# Sheet_1_2024-11-01.net
KiCad netlist of a schematic drawn in Altium Designer
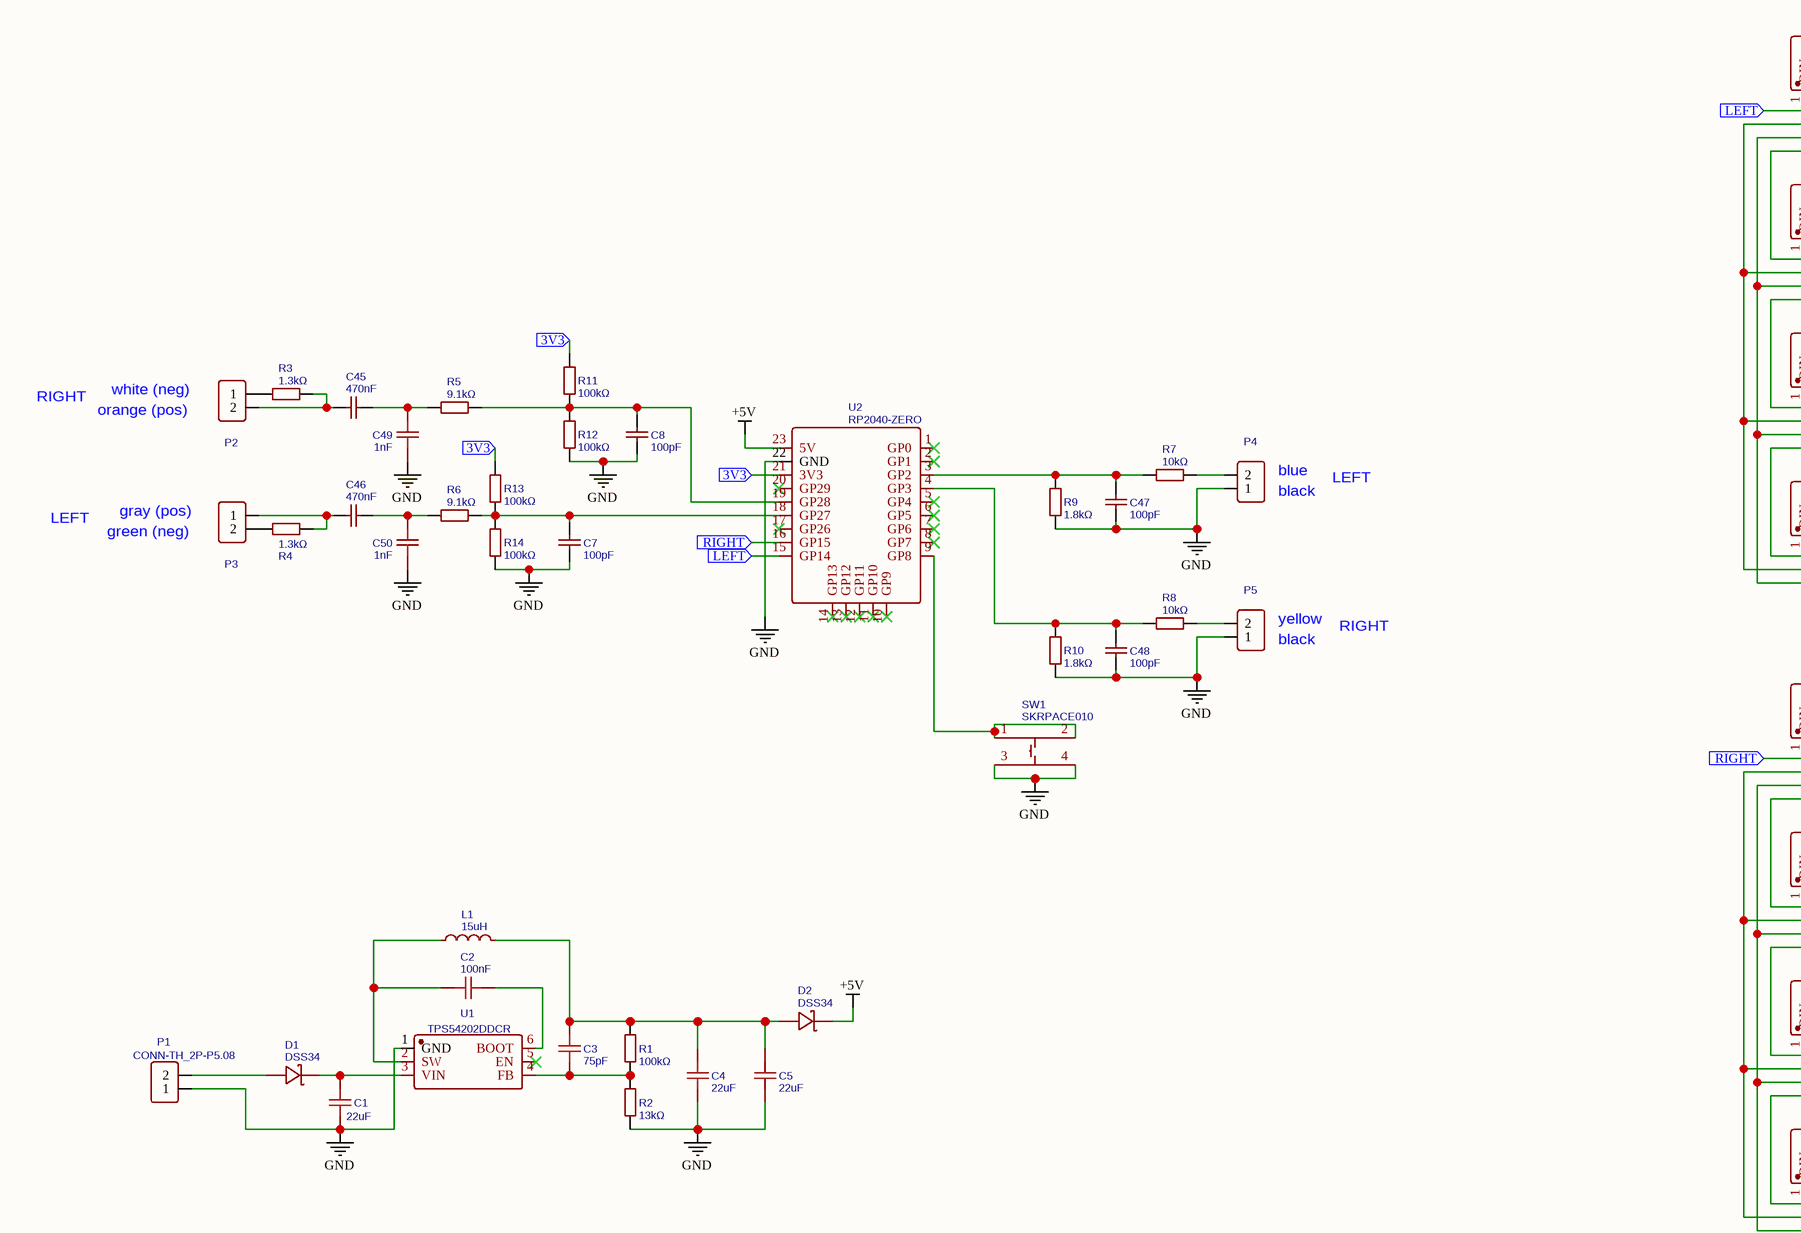
[diagram p0: Sheet_1_2024-11-01.schdoc, left]
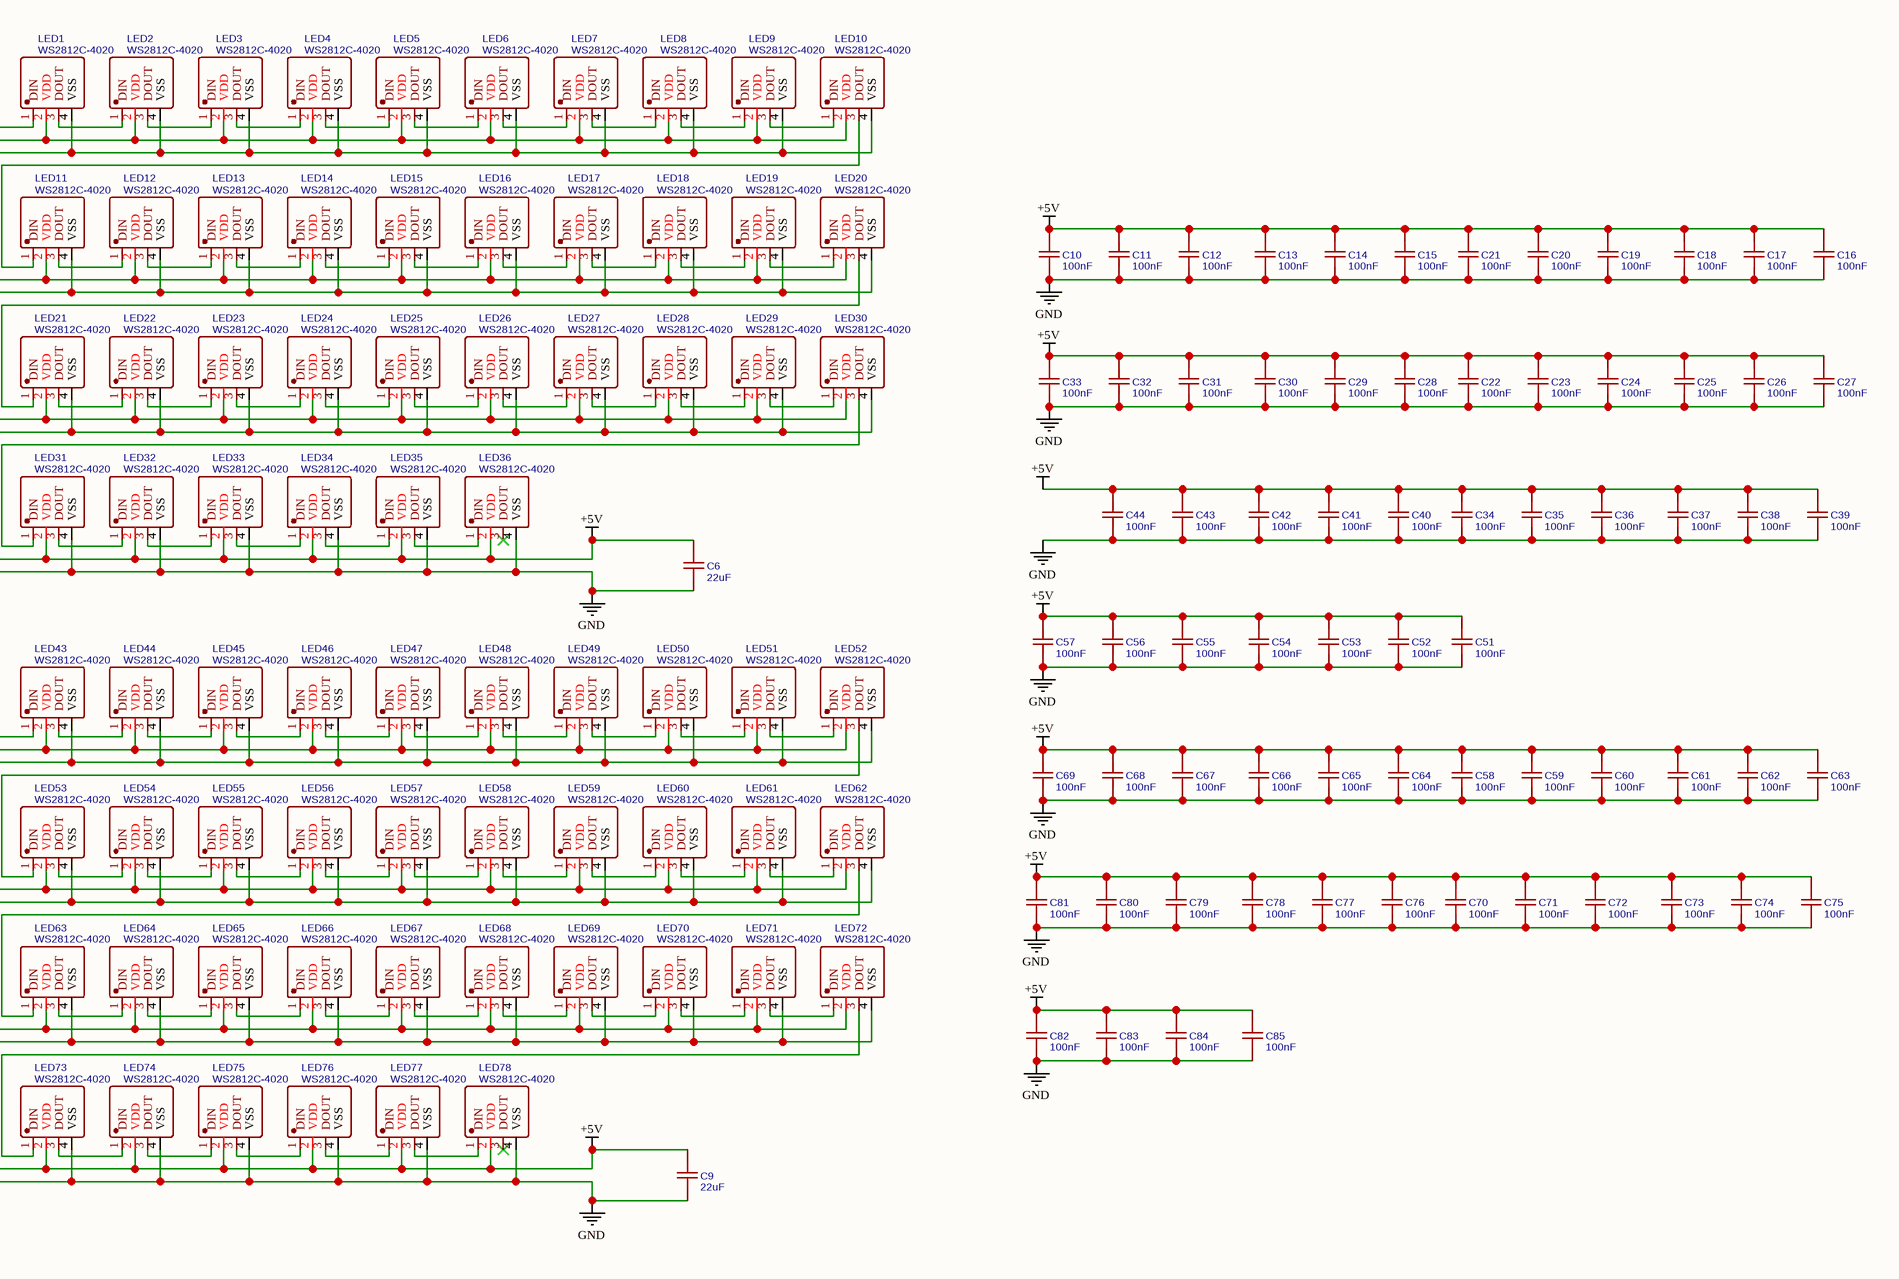
[diagram p1: Sheet_1_2024-11-01.schdoc, right]

(export (version "E")
  (design (tool "Eeschema 10.0.6"))
  (components
    (comp (ref "C1")
      (value "22uF")
      (fields
        (field (name "MANUFACTURER") "Samsung Electro-Mechanics")
        (field (name "MANUFACTURER PART") "CL21A226MAYNNNE")
        (field (name "CONTRIBUTOR") "LCSC")
      )
      (libsource (lib "altium-import") (part "root_1_22uF_"))
    )
    (comp (ref "C2")
      (value "100nF")
      (fields
        (field (name "MANUFACTURER PART") "CL05B104KO5NNNC")
        (field (name "MANUFACTURER") "SAMSUNG(三星)")
      )
      (libsource (lib "altium-import") (part "root_2_100nF_"))
    )
    (comp (ref "C3")
      (value "75pF")
      (fields
        (field (name "MANUFACTURER") "YAGEO(国巨)")
        (field (name "MANUFACTURER PART") "CC0603JRNPO9BN750")
        (field (name "CONTRIBUTOR") "LCSC")
      )
      (libsource (lib "altium-import") (part "root_0_75pF_"))
    )
    (comp (ref "C4")
      (value "22uF")
      (fields (field (name "MANUFACTURER") "SAMSUNG") (field (name "MANUFACTURER PART") "CL10A226MQ8NRNC"))
      (libsource (lib "altium-import") (part "root_1_22uF_"))
    )
    (comp (ref "C5")
      (value "22uF")
      (fields (field (name "MANUFACTURER") "SAMSUNG") (field (name "MANUFACTURER PART") "CL10A226MQ8NRNC"))
      (libsource (lib "altium-import") (part "root_1_22uF_"))
    )
    (comp (ref "C6")
      (value "22uF")
      (fields (field (name "MANUFACTURER") "SAMSUNG") (field (name "MANUFACTURER PART") "CL10A226MQ8NRNC"))
      (libsource (lib "altium-import") (part "root_1_22uF_"))
    )
    (comp (ref "C7")
      (value "100pF")
      (fields
        (field (name "MANUFACTURER PART") "CL10C101JB8NNNC")
        (field (name "MANUFACTURER") "SAMSUNG(三星)")
      )
      (libsource (lib "altium-import") (part "root_1_100pF_"))
    )
    (comp (ref "C8")
      (value "100pF")
      (fields
        (field (name "MANUFACTURER PART") "CL10C101JB8NNNC")
        (field (name "MANUFACTURER") "SAMSUNG(三星)")
      )
      (libsource (lib "altium-import") (part "root_1_100pF_"))
    )
    (comp (ref "C9")
      (value "22uF")
      (fields (field (name "MANUFACTURER") "SAMSUNG") (field (name "MANUFACTURER PART") "CL10A226MQ8NRNC"))
      (libsource (lib "altium-import") (part "root_1_22uF_"))
    )
    (comp (ref "C10")
      (value "100nF")
      (fields
        (field (name "MANUFACTURER PART") "CL05B104KO5NNNC")
        (field (name "MANUFACTURER") "SAMSUNG(三星)")
      )
      (libsource (lib "altium-import") (part "root_1_100nF_"))
    )
    (comp (ref "C11")
      (value "100nF")
      (fields
        (field (name "MANUFACTURER PART") "CL05B104KO5NNNC")
        (field (name "MANUFACTURER") "SAMSUNG(三星)")
      )
      (libsource (lib "altium-import") (part "root_1_100nF_"))
    )
    (comp (ref "C12")
      (value "100nF")
      (fields
        (field (name "MANUFACTURER PART") "CL05B104KO5NNNC")
        (field (name "MANUFACTURER") "SAMSUNG(三星)")
      )
      (libsource (lib "altium-import") (part "root_1_100nF_"))
    )
    (comp (ref "C13")
      (value "100nF")
      (fields
        (field (name "MANUFACTURER PART") "CL05B104KO5NNNC")
        (field (name "MANUFACTURER") "SAMSUNG(三星)")
      )
      (libsource (lib "altium-import") (part "root_1_100nF_"))
    )
    (comp (ref "C14")
      (value "100nF")
      (fields
        (field (name "MANUFACTURER PART") "CL05B104KO5NNNC")
        (field (name "MANUFACTURER") "SAMSUNG(三星)")
      )
      (libsource (lib "altium-import") (part "root_1_100nF_"))
    )
    (comp (ref "C15")
      (value "100nF")
      (fields
        (field (name "MANUFACTURER PART") "CL05B104KO5NNNC")
        (field (name "MANUFACTURER") "SAMSUNG(三星)")
      )
      (libsource (lib "altium-import") (part "root_1_100nF_"))
    )
    (comp (ref "C16")
      (value "100nF")
      (fields
        (field (name "MANUFACTURER PART") "CL05B104KO5NNNC")
        (field (name "MANUFACTURER") "SAMSUNG(三星)")
      )
      (libsource (lib "altium-import") (part "root_1_100nF_"))
    )
    (comp (ref "C17")
      (value "100nF")
      (fields
        (field (name "MANUFACTURER PART") "CL05B104KO5NNNC")
        (field (name "MANUFACTURER") "SAMSUNG(三星)")
      )
      (libsource (lib "altium-import") (part "root_1_100nF_"))
    )
    (comp (ref "C18")
      (value "100nF")
      (fields
        (field (name "MANUFACTURER PART") "CL05B104KO5NNNC")
        (field (name "MANUFACTURER") "SAMSUNG(三星)")
      )
      (libsource (lib "altium-import") (part "root_1_100nF_"))
    )
    (comp (ref "C19")
      (value "100nF")
      (fields
        (field (name "MANUFACTURER PART") "CL05B104KO5NNNC")
        (field (name "MANUFACTURER") "SAMSUNG(三星)")
      )
      (libsource (lib "altium-import") (part "root_1_100nF_"))
    )
    (comp (ref "C20")
      (value "100nF")
      (fields
        (field (name "MANUFACTURER PART") "CL05B104KO5NNNC")
        (field (name "MANUFACTURER") "SAMSUNG(三星)")
      )
      (libsource (lib "altium-import") (part "root_1_100nF_"))
    )
    (comp (ref "C21")
      (value "100nF")
      (fields
        (field (name "MANUFACTURER PART") "CL05B104KO5NNNC")
        (field (name "MANUFACTURER") "SAMSUNG(三星)")
      )
      (libsource (lib "altium-import") (part "root_1_100nF_"))
    )
    (comp (ref "C22")
      (value "100nF")
      (fields
        (field (name "MANUFACTURER PART") "CL05B104KO5NNNC")
        (field (name "MANUFACTURER") "SAMSUNG(三星)")
      )
      (libsource (lib "altium-import") (part "root_1_100nF_"))
    )
    (comp (ref "C23")
      (value "100nF")
      (fields
        (field (name "MANUFACTURER PART") "CL05B104KO5NNNC")
        (field (name "MANUFACTURER") "SAMSUNG(三星)")
      )
      (libsource (lib "altium-import") (part "root_1_100nF_"))
    )
    (comp (ref "C24")
      (value "100nF")
      (fields
        (field (name "MANUFACTURER PART") "CL05B104KO5NNNC")
        (field (name "MANUFACTURER") "SAMSUNG(三星)")
      )
      (libsource (lib "altium-import") (part "root_1_100nF_"))
    )
    (comp (ref "C25")
      (value "100nF")
      (fields
        (field (name "MANUFACTURER PART") "CL05B104KO5NNNC")
        (field (name "MANUFACTURER") "SAMSUNG(三星)")
      )
      (libsource (lib "altium-import") (part "root_1_100nF_"))
    )
    (comp (ref "C26")
      (value "100nF")
      (fields
        (field (name "MANUFACTURER PART") "CL05B104KO5NNNC")
        (field (name "MANUFACTURER") "SAMSUNG(三星)")
      )
      (libsource (lib "altium-import") (part "root_1_100nF_"))
    )
    (comp (ref "C27")
      (value "100nF")
      (fields
        (field (name "MANUFACTURER PART") "CL05B104KO5NNNC")
        (field (name "MANUFACTURER") "SAMSUNG(三星)")
      )
      (libsource (lib "altium-import") (part "root_1_100nF_"))
    )
    (comp (ref "C28")
      (value "100nF")
      (fields
        (field (name "MANUFACTURER PART") "CL05B104KO5NNNC")
        (field (name "MANUFACTURER") "SAMSUNG(三星)")
      )
      (libsource (lib "altium-import") (part "root_1_100nF_"))
    )
    (comp (ref "C29")
      (value "100nF")
      (fields
        (field (name "MANUFACTURER PART") "CL05B104KO5NNNC")
        (field (name "MANUFACTURER") "SAMSUNG(三星)")
      )
      (libsource (lib "altium-import") (part "root_1_100nF_"))
    )
    (comp (ref "C30")
      (value "100nF")
      (fields
        (field (name "MANUFACTURER PART") "CL05B104KO5NNNC")
        (field (name "MANUFACTURER") "SAMSUNG(三星)")
      )
      (libsource (lib "altium-import") (part "root_1_100nF_"))
    )
    (comp (ref "C31")
      (value "100nF")
      (fields
        (field (name "MANUFACTURER PART") "CL05B104KO5NNNC")
        (field (name "MANUFACTURER") "SAMSUNG(三星)")
      )
      (libsource (lib "altium-import") (part "root_1_100nF_"))
    )
    (comp (ref "C32")
      (value "100nF")
      (fields
        (field (name "MANUFACTURER PART") "CL05B104KO5NNNC")
        (field (name "MANUFACTURER") "SAMSUNG(三星)")
      )
      (libsource (lib "altium-import") (part "root_1_100nF_"))
    )
    (comp (ref "C33")
      (value "100nF")
      (fields
        (field (name "MANUFACTURER PART") "CL05B104KO5NNNC")
        (field (name "MANUFACTURER") "SAMSUNG(三星)")
      )
      (libsource (lib "altium-import") (part "root_1_100nF_"))
    )
    (comp (ref "C34")
      (value "100nF")
      (fields
        (field (name "MANUFACTURER PART") "CL05B104KO5NNNC")
        (field (name "MANUFACTURER") "SAMSUNG(三星)")
      )
      (libsource (lib "altium-import") (part "root_1_100nF_"))
    )
    (comp (ref "C35")
      (value "100nF")
      (fields
        (field (name "MANUFACTURER PART") "CL05B104KO5NNNC")
        (field (name "MANUFACTURER") "SAMSUNG(三星)")
      )
      (libsource (lib "altium-import") (part "root_1_100nF_"))
    )
    (comp (ref "C36")
      (value "100nF")
      (fields
        (field (name "MANUFACTURER PART") "CL05B104KO5NNNC")
        (field (name "MANUFACTURER") "SAMSUNG(三星)")
      )
      (libsource (lib "altium-import") (part "root_1_100nF_"))
    )
    (comp (ref "C37")
      (value "100nF")
      (fields
        (field (name "MANUFACTURER PART") "CL05B104KO5NNNC")
        (field (name "MANUFACTURER") "SAMSUNG(三星)")
      )
      (libsource (lib "altium-import") (part "root_1_100nF_"))
    )
    (comp (ref "C38")
      (value "100nF")
      (fields
        (field (name "MANUFACTURER PART") "CL05B104KO5NNNC")
        (field (name "MANUFACTURER") "SAMSUNG(三星)")
      )
      (libsource (lib "altium-import") (part "root_1_100nF_"))
    )
    (comp (ref "C39")
      (value "100nF")
      (fields
        (field (name "MANUFACTURER PART") "CL05B104KO5NNNC")
        (field (name "MANUFACTURER") "SAMSUNG(三星)")
      )
      (libsource (lib "altium-import") (part "root_1_100nF_"))
    )
    (comp (ref "C40")
      (value "100nF")
      (fields
        (field (name "MANUFACTURER PART") "CL05B104KO5NNNC")
        (field (name "MANUFACTURER") "SAMSUNG(三星)")
      )
      (libsource (lib "altium-import") (part "root_1_100nF_"))
    )
    (comp (ref "C41")
      (value "100nF")
      (fields
        (field (name "MANUFACTURER PART") "CL05B104KO5NNNC")
        (field (name "MANUFACTURER") "SAMSUNG(三星)")
      )
      (libsource (lib "altium-import") (part "root_1_100nF_"))
    )
    (comp (ref "C42")
      (value "100nF")
      (fields
        (field (name "MANUFACTURER PART") "CL05B104KO5NNNC")
        (field (name "MANUFACTURER") "SAMSUNG(三星)")
      )
      (libsource (lib "altium-import") (part "root_1_100nF_"))
    )
    (comp (ref "C43")
      (value "100nF")
      (fields
        (field (name "MANUFACTURER PART") "CL05B104KO5NNNC")
        (field (name "MANUFACTURER") "SAMSUNG(三星)")
      )
      (libsource (lib "altium-import") (part "root_1_100nF_"))
    )
    (comp (ref "C44")
      (value "100nF")
      (fields
        (field (name "MANUFACTURER PART") "CL05B104KO5NNNC")
        (field (name "MANUFACTURER") "SAMSUNG(三星)")
      )
      (libsource (lib "altium-import") (part "root_1_100nF_"))
    )
    (comp (ref "C45")
      (value "470nF")
      (fields
        (field (name "MANUFACTURER PART") "CL21B474KBFNNNE")
        (field (name "MANUFACTURER") "SAMSUNG(三星)")
      )
      (libsource (lib "altium-import") (part "root_0_470nF_"))
    )
    (comp (ref "C46")
      (value "470nF")
      (fields
        (field (name "MANUFACTURER PART") "CL21B474KBFNNNE")
        (field (name "MANUFACTURER") "SAMSUNG(三星)")
      )
      (libsource (lib "altium-import") (part "root_0_470nF_"))
    )
    (comp (ref "C47")
      (value "100pF")
      (fields
        (field (name "MANUFACTURER PART") "CL10C101JB8NNNC")
        (field (name "MANUFACTURER") "SAMSUNG(三星)")
      )
      (libsource (lib "altium-import") (part "root_1_100pF_"))
    )
    (comp (ref "C48")
      (value "100pF")
      (fields
        (field (name "MANUFACTURER PART") "CL10C101JB8NNNC")
        (field (name "MANUFACTURER") "SAMSUNG(三星)")
      )
      (libsource (lib "altium-import") (part "root_1_100pF_"))
    )
    (comp (ref "C49")
      (value "1nF")
      (fields
        (field (name "MANUFACTURER") "SAMSUNG(三星)")
        (field (name "MANUFACTURER PART") "CL10C102JB8NNNC")
        (field (name "CONTRIBUTOR") "LCSC")
      )
      (libsource (lib "altium-import") (part "root_1_1nF_"))
    )
    (comp (ref "C50")
      (value "1nF")
      (fields
        (field (name "MANUFACTURER") "SAMSUNG(三星)")
        (field (name "MANUFACTURER PART") "CL10C102JB8NNNC")
        (field (name "CONTRIBUTOR") "LCSC")
      )
      (libsource (lib "altium-import") (part "root_1_1nF_"))
    )
    (comp (ref "C51")
      (value "100nF")
      (fields
        (field (name "MANUFACTURER PART") "CL05B104KO5NNNC")
        (field (name "MANUFACTURER") "SAMSUNG(三星)")
      )
      (libsource (lib "altium-import") (part "root_1_100nF_"))
    )
    (comp (ref "C52")
      (value "100nF")
      (fields
        (field (name "MANUFACTURER PART") "CL05B104KO5NNNC")
        (field (name "MANUFACTURER") "SAMSUNG(三星)")
      )
      (libsource (lib "altium-import") (part "root_1_100nF_"))
    )
    (comp (ref "C53")
      (value "100nF")
      (fields
        (field (name "MANUFACTURER PART") "CL05B104KO5NNNC")
        (field (name "MANUFACTURER") "SAMSUNG(三星)")
      )
      (libsource (lib "altium-import") (part "root_1_100nF_"))
    )
    (comp (ref "C54")
      (value "100nF")
      (fields
        (field (name "MANUFACTURER PART") "CL05B104KO5NNNC")
        (field (name "MANUFACTURER") "SAMSUNG(三星)")
      )
      (libsource (lib "altium-import") (part "root_1_100nF_"))
    )
    (comp (ref "C55")
      (value "100nF")
      (fields
        (field (name "MANUFACTURER PART") "CL05B104KO5NNNC")
        (field (name "MANUFACTURER") "SAMSUNG(三星)")
      )
      (libsource (lib "altium-import") (part "root_1_100nF_"))
    )
    (comp (ref "C56")
      (value "100nF")
      (fields
        (field (name "MANUFACTURER PART") "CL05B104KO5NNNC")
        (field (name "MANUFACTURER") "SAMSUNG(三星)")
      )
      (libsource (lib "altium-import") (part "root_1_100nF_"))
    )
    (comp (ref "C57")
      (value "100nF")
      (fields
        (field (name "MANUFACTURER PART") "CL05B104KO5NNNC")
        (field (name "MANUFACTURER") "SAMSUNG(三星)")
      )
      (libsource (lib "altium-import") (part "root_1_100nF_"))
    )
    (comp (ref "C58")
      (value "100nF")
      (fields
        (field (name "MANUFACTURER PART") "CL05B104KO5NNNC")
        (field (name "MANUFACTURER") "SAMSUNG(三星)")
      )
      (libsource (lib "altium-import") (part "root_1_100nF_"))
    )
    (comp (ref "C59")
      (value "100nF")
      (fields
        (field (name "MANUFACTURER PART") "CL05B104KO5NNNC")
        (field (name "MANUFACTURER") "SAMSUNG(三星)")
      )
      (libsource (lib "altium-import") (part "root_1_100nF_"))
    )
    (comp (ref "C60")
      (value "100nF")
      (fields
        (field (name "MANUFACTURER PART") "CL05B104KO5NNNC")
        (field (name "MANUFACTURER") "SAMSUNG(三星)")
      )
      (libsource (lib "altium-import") (part "root_1_100nF_"))
    )
    (comp (ref "C61")
      (value "100nF")
      (fields
        (field (name "MANUFACTURER PART") "CL05B104KO5NNNC")
        (field (name "MANUFACTURER") "SAMSUNG(三星)")
      )
      (libsource (lib "altium-import") (part "root_1_100nF_"))
    )
    (comp (ref "C62")
      (value "100nF")
      (fields
        (field (name "MANUFACTURER PART") "CL05B104KO5NNNC")
        (field (name "MANUFACTURER") "SAMSUNG(三星)")
      )
      (libsource (lib "altium-import") (part "root_1_100nF_"))
    )
    (comp (ref "C63")
      (value "100nF")
      (fields
        (field (name "MANUFACTURER PART") "CL05B104KO5NNNC")
        (field (name "MANUFACTURER") "SAMSUNG(三星)")
      )
      (libsource (lib "altium-import") (part "root_1_100nF_"))
    )
    (comp (ref "C64")
      (value "100nF")
      (fields
        (field (name "MANUFACTURER PART") "CL05B104KO5NNNC")
        (field (name "MANUFACTURER") "SAMSUNG(三星)")
      )
      (libsource (lib "altium-import") (part "root_1_100nF_"))
    )
    (comp (ref "C65")
      (value "100nF")
      (fields
        (field (name "MANUFACTURER PART") "CL05B104KO5NNNC")
        (field (name "MANUFACTURER") "SAMSUNG(三星)")
      )
      (libsource (lib "altium-import") (part "root_1_100nF_"))
    )
    (comp (ref "C66")
      (value "100nF")
      (fields
        (field (name "MANUFACTURER PART") "CL05B104KO5NNNC")
        (field (name "MANUFACTURER") "SAMSUNG(三星)")
      )
      (libsource (lib "altium-import") (part "root_1_100nF_"))
    )
    (comp (ref "C67")
      (value "100nF")
      (fields
        (field (name "MANUFACTURER PART") "CL05B104KO5NNNC")
        (field (name "MANUFACTURER") "SAMSUNG(三星)")
      )
      (libsource (lib "altium-import") (part "root_1_100nF_"))
    )
    (comp (ref "C68")
      (value "100nF")
      (fields
        (field (name "MANUFACTURER PART") "CL05B104KO5NNNC")
        (field (name "MANUFACTURER") "SAMSUNG(三星)")
      )
      (libsource (lib "altium-import") (part "root_1_100nF_"))
    )
    (comp (ref "C69")
      (value "100nF")
      (fields
        (field (name "MANUFACTURER PART") "CL05B104KO5NNNC")
        (field (name "MANUFACTURER") "SAMSUNG(三星)")
      )
      (libsource (lib "altium-import") (part "root_1_100nF_"))
    )
    (comp (ref "C70")
      (value "100nF")
      (fields
        (field (name "MANUFACTURER PART") "CL05B104KO5NNNC")
        (field (name "MANUFACTURER") "SAMSUNG(三星)")
      )
      (libsource (lib "altium-import") (part "root_1_100nF_"))
    )
    (comp (ref "C71")
      (value "100nF")
      (fields
        (field (name "MANUFACTURER PART") "CL05B104KO5NNNC")
        (field (name "MANUFACTURER") "SAMSUNG(三星)")
      )
      (libsource (lib "altium-import") (part "root_1_100nF_"))
    )
    (comp (ref "C72")
      (value "100nF")
      (fields
        (field (name "MANUFACTURER PART") "CL05B104KO5NNNC")
        (field (name "MANUFACTURER") "SAMSUNG(三星)")
      )
      (libsource (lib "altium-import") (part "root_1_100nF_"))
    )
    (comp (ref "C73")
      (value "100nF")
      (fields
        (field (name "MANUFACTURER PART") "CL05B104KO5NNNC")
        (field (name "MANUFACTURER") "SAMSUNG(三星)")
      )
      (libsource (lib "altium-import") (part "root_1_100nF_"))
    )
    (comp (ref "C74")
      (value "100nF")
      (fields
        (field (name "MANUFACTURER PART") "CL05B104KO5NNNC")
        (field (name "MANUFACTURER") "SAMSUNG(三星)")
      )
      (libsource (lib "altium-import") (part "root_1_100nF_"))
    )
    (comp (ref "C75")
      (value "100nF")
      (fields
        (field (name "MANUFACTURER PART") "CL05B104KO5NNNC")
        (field (name "MANUFACTURER") "SAMSUNG(三星)")
      )
      (libsource (lib "altium-import") (part "root_1_100nF_"))
    )
    (comp (ref "C76")
      (value "100nF")
      (fields
        (field (name "MANUFACTURER PART") "CL05B104KO5NNNC")
        (field (name "MANUFACTURER") "SAMSUNG(三星)")
      )
      (libsource (lib "altium-import") (part "root_1_100nF_"))
    )
    (comp (ref "C77")
      (value "100nF")
      (fields
        (field (name "MANUFACTURER PART") "CL05B104KO5NNNC")
        (field (name "MANUFACTURER") "SAMSUNG(三星)")
      )
      (libsource (lib "altium-import") (part "root_1_100nF_"))
    )
    (comp (ref "C78")
      (value "100nF")
      (fields
        (field (name "MANUFACTURER PART") "CL05B104KO5NNNC")
        (field (name "MANUFACTURER") "SAMSUNG(三星)")
      )
      (libsource (lib "altium-import") (part "root_1_100nF_"))
    )
    (comp (ref "C79")
      (value "100nF")
      (fields
        (field (name "MANUFACTURER PART") "CL05B104KO5NNNC")
        (field (name "MANUFACTURER") "SAMSUNG(三星)")
      )
      (libsource (lib "altium-import") (part "root_1_100nF_"))
    )
    (comp (ref "C80")
      (value "100nF")
      (fields
        (field (name "MANUFACTURER PART") "CL05B104KO5NNNC")
        (field (name "MANUFACTURER") "SAMSUNG(三星)")
      )
      (libsource (lib "altium-import") (part "root_1_100nF_"))
    )
    (comp (ref "C81")
      (value "100nF")
      (fields
        (field (name "MANUFACTURER PART") "CL05B104KO5NNNC")
        (field (name "MANUFACTURER") "SAMSUNG(三星)")
      )
      (libsource (lib "altium-import") (part "root_1_100nF_"))
    )
    (comp (ref "C82")
      (value "100nF")
      (fields
        (field (name "MANUFACTURER PART") "CL05B104KO5NNNC")
        (field (name "MANUFACTURER") "SAMSUNG(三星)")
      )
      (libsource (lib "altium-import") (part "root_1_100nF_"))
    )
    (comp (ref "C83")
      (value "100nF")
      (fields
        (field (name "MANUFACTURER PART") "CL05B104KO5NNNC")
        (field (name "MANUFACTURER") "SAMSUNG(三星)")
      )
      (libsource (lib "altium-import") (part "root_1_100nF_"))
    )
    (comp (ref "C84")
      (value "100nF")
      (fields
        (field (name "MANUFACTURER PART") "CL05B104KO5NNNC")
        (field (name "MANUFACTURER") "SAMSUNG(三星)")
      )
      (libsource (lib "altium-import") (part "root_1_100nF_"))
    )
    (comp (ref "C85")
      (value "100nF")
      (fields
        (field (name "MANUFACTURER PART") "CL05B104KO5NNNC")
        (field (name "MANUFACTURER") "SAMSUNG(三星)")
      )
      (libsource (lib "altium-import") (part "root_1_100nF_"))
    )
    (comp (ref "D1")
      (value "DSS34")
      (fields (field (name "MANUFACTURER") "STARSEA"))
      (libsource (lib "altium-import") (part "root_2_DSS34_"))
    )
    (comp (ref "D2")
      (value "DSS34")
      (fields (field (name "MANUFACTURER") "STARSEA"))
      (libsource (lib "altium-import") (part "root_2_DSS34_"))
    )
    (comp (ref "L1")
      (value "15uH")
      (fields
        (field (name "MANUFACTURER") "Sunltech(韩国顺磁)")
        (field (name "MANUFACTURER PART") "SLP6028S150MTT")
        (field (name "CONTRIBUTOR") "LCSC")
      )
      (libsource (lib "altium-import") (part "root_0_15uH_"))
    )
    (comp (ref "LED1")
      (value "WS2812C-4020")
      (fields (field (name "MANUFACTURER") "worldsemi") (field (name "CONTRIBUTOR") "lcsc"))
      (libsource (lib "altium-import") (part "root_1_WS2812C-4020_"))
    )
    (comp (ref "LED2")
      (value "WS2812C-4020")
      (fields (field (name "MANUFACTURER") "worldsemi") (field (name "CONTRIBUTOR") "lcsc"))
      (libsource (lib "altium-import") (part "root_1_WS2812C-4020_"))
    )
    (comp (ref "LED3")
      (value "WS2812C-4020")
      (fields (field (name "MANUFACTURER") "worldsemi") (field (name "CONTRIBUTOR") "lcsc"))
      (libsource (lib "altium-import") (part "root_1_WS2812C-4020_"))
    )
    (comp (ref "LED4")
      (value "WS2812C-4020")
      (fields (field (name "MANUFACTURER") "worldsemi") (field (name "CONTRIBUTOR") "lcsc"))
      (libsource (lib "altium-import") (part "root_1_WS2812C-4020_"))
    )
    (comp (ref "LED5")
      (value "WS2812C-4020")
      (fields (field (name "MANUFACTURER") "worldsemi") (field (name "CONTRIBUTOR") "lcsc"))
      (libsource (lib "altium-import") (part "root_1_WS2812C-4020_"))
    )
    (comp (ref "LED6")
      (value "WS2812C-4020")
      (fields (field (name "MANUFACTURER") "worldsemi") (field (name "CONTRIBUTOR") "lcsc"))
      (libsource (lib "altium-import") (part "root_1_WS2812C-4020_"))
    )
    (comp (ref "LED7")
      (value "WS2812C-4020")
      (fields (field (name "MANUFACTURER") "worldsemi") (field (name "CONTRIBUTOR") "lcsc"))
      (libsource (lib "altium-import") (part "root_1_WS2812C-4020_"))
    )
    (comp (ref "LED8")
      (value "WS2812C-4020")
      (fields (field (name "MANUFACTURER") "worldsemi") (field (name "CONTRIBUTOR") "lcsc"))
      (libsource (lib "altium-import") (part "root_1_WS2812C-4020_"))
    )
    (comp (ref "LED9")
      (value "WS2812C-4020")
      (fields (field (name "MANUFACTURER") "worldsemi") (field (name "CONTRIBUTOR") "lcsc"))
      (libsource (lib "altium-import") (part "root_1_WS2812C-4020_"))
    )
    (comp (ref "LED10")
      (value "WS2812C-4020")
      (fields (field (name "MANUFACTURER") "worldsemi") (field (name "CONTRIBUTOR") "lcsc"))
      (libsource (lib "altium-import") (part "root_1_WS2812C-4020_"))
    )
    (comp (ref "LED11")
      (value "WS2812C-4020")
      (fields (field (name "MANUFACTURER") "worldsemi") (field (name "CONTRIBUTOR") "lcsc"))
      (libsource (lib "altium-import") (part "root_1_WS2812C-4020_"))
    )
    (comp (ref "LED12")
      (value "WS2812C-4020")
      (fields (field (name "MANUFACTURER") "worldsemi") (field (name "CONTRIBUTOR") "lcsc"))
      (libsource (lib "altium-import") (part "root_1_WS2812C-4020_"))
    )
    (comp (ref "LED13")
      (value "WS2812C-4020")
      (fields (field (name "MANUFACTURER") "worldsemi") (field (name "CONTRIBUTOR") "lcsc"))
      (libsource (lib "altium-import") (part "root_1_WS2812C-4020_"))
    )
    (comp (ref "LED14")
      (value "WS2812C-4020")
      (fields (field (name "MANUFACTURER") "worldsemi") (field (name "CONTRIBUTOR") "lcsc"))
      (libsource (lib "altium-import") (part "root_1_WS2812C-4020_"))
    )
    (comp (ref "LED15")
      (value "WS2812C-4020")
      (fields (field (name "MANUFACTURER") "worldsemi") (field (name "CONTRIBUTOR") "lcsc"))
      (libsource (lib "altium-import") (part "root_1_WS2812C-4020_"))
    )
    (comp (ref "LED16")
      (value "WS2812C-4020")
      (fields (field (name "MANUFACTURER") "worldsemi") (field (name "CONTRIBUTOR") "lcsc"))
      (libsource (lib "altium-import") (part "root_1_WS2812C-4020_"))
    )
    (comp (ref "LED17")
      (value "WS2812C-4020")
      (fields (field (name "MANUFACTURER") "worldsemi") (field (name "CONTRIBUTOR") "lcsc"))
      (libsource (lib "altium-import") (part "root_1_WS2812C-4020_"))
    )
    (comp (ref "LED18")
      (value "WS2812C-4020")
      (fields (field (name "MANUFACTURER") "worldsemi") (field (name "CONTRIBUTOR") "lcsc"))
      (libsource (lib "altium-import") (part "root_1_WS2812C-4020_"))
    )
    (comp (ref "LED19")
      (value "WS2812C-4020")
      (fields (field (name "MANUFACTURER") "worldsemi") (field (name "CONTRIBUTOR") "lcsc"))
      (libsource (lib "altium-import") (part "root_1_WS2812C-4020_"))
    )
    (comp (ref "LED20")
      (value "WS2812C-4020")
      (fields (field (name "MANUFACTURER") "worldsemi") (field (name "CONTRIBUTOR") "lcsc"))
      (libsource (lib "altium-import") (part "root_1_WS2812C-4020_"))
    )
    (comp (ref "LED21")
      (value "WS2812C-4020")
      (fields (field (name "MANUFACTURER") "worldsemi") (field (name "CONTRIBUTOR") "lcsc"))
      (libsource (lib "altium-import") (part "root_1_WS2812C-4020_"))
    )
    (comp (ref "LED22")
      (value "WS2812C-4020")
      (fields (field (name "MANUFACTURER") "worldsemi") (field (name "CONTRIBUTOR") "lcsc"))
      (libsource (lib "altium-import") (part "root_1_WS2812C-4020_"))
    )
    (comp (ref "LED23")
      (value "WS2812C-4020")
      (fields (field (name "MANUFACTURER") "worldsemi") (field (name "CONTRIBUTOR") "lcsc"))
      (libsource (lib "altium-import") (part "root_1_WS2812C-4020_"))
    )
    (comp (ref "LED24")
      (value "WS2812C-4020")
      (fields (field (name "MANUFACTURER") "worldsemi") (field (name "CONTRIBUTOR") "lcsc"))
      (libsource (lib "altium-import") (part "root_1_WS2812C-4020_"))
    )
    (comp (ref "LED25")
      (value "WS2812C-4020")
      (fields (field (name "MANUFACTURER") "worldsemi") (field (name "CONTRIBUTOR") "lcsc"))
      (libsource (lib "altium-import") (part "root_1_WS2812C-4020_"))
    )
    (comp (ref "LED26")
      (value "WS2812C-4020")
      (fields (field (name "MANUFACTURER") "worldsemi") (field (name "CONTRIBUTOR") "lcsc"))
      (libsource (lib "altium-import") (part "root_1_WS2812C-4020_"))
    )
    (comp (ref "LED27")
      (value "WS2812C-4020")
      (fields (field (name "MANUFACTURER") "worldsemi") (field (name "CONTRIBUTOR") "lcsc"))
      (libsource (lib "altium-import") (part "root_1_WS2812C-4020_"))
    )
    (comp (ref "LED28")
      (value "WS2812C-4020")
      (fields (field (name "MANUFACTURER") "worldsemi") (field (name "CONTRIBUTOR") "lcsc"))
      (libsource (lib "altium-import") (part "root_1_WS2812C-4020_"))
    )
    (comp (ref "LED29")
      (value "WS2812C-4020")
      (fields (field (name "MANUFACTURER") "worldsemi") (field (name "CONTRIBUTOR") "lcsc"))
      (libsource (lib "altium-import") (part "root_1_WS2812C-4020_"))
    )
    (comp (ref "LED30")
      (value "WS2812C-4020")
      (fields (field (name "MANUFACTURER") "worldsemi") (field (name "CONTRIBUTOR") "lcsc"))
      (libsource (lib "altium-import") (part "root_1_WS2812C-4020_"))
    )
    (comp (ref "LED31")
      (value "WS2812C-4020")
      (fields (field (name "MANUFACTURER") "worldsemi") (field (name "CONTRIBUTOR") "lcsc"))
      (libsource (lib "altium-import") (part "root_1_WS2812C-4020_"))
    )
    (comp (ref "LED32")
      (value "WS2812C-4020")
      (fields (field (name "MANUFACTURER") "worldsemi") (field (name "CONTRIBUTOR") "lcsc"))
      (libsource (lib "altium-import") (part "root_1_WS2812C-4020_"))
    )
    (comp (ref "LED33")
      (value "WS2812C-4020")
      (fields (field (name "MANUFACTURER") "worldsemi") (field (name "CONTRIBUTOR") "lcsc"))
      (libsource (lib "altium-import") (part "root_1_WS2812C-4020_"))
    )
    (comp (ref "LED34")
      (value "WS2812C-4020")
      (fields (field (name "MANUFACTURER") "worldsemi") (field (name "CONTRIBUTOR") "lcsc"))
      (libsource (lib "altium-import") (part "root_1_WS2812C-4020_"))
    )
    (comp (ref "LED35")
      (value "WS2812C-4020")
      (fields (field (name "MANUFACTURER") "worldsemi") (field (name "CONTRIBUTOR") "lcsc"))
      (libsource (lib "altium-import") (part "root_1_WS2812C-4020_"))
    )
    (comp (ref "LED36")
      (value "WS2812C-4020")
      (fields (field (name "MANUFACTURER") "worldsemi") (field (name "CONTRIBUTOR") "lcsc"))
      (libsource (lib "altium-import") (part "root_1_WS2812C-4020_"))
    )
    (comp (ref "LED43")
      (value "WS2812C-4020")
      (fields (field (name "MANUFACTURER") "worldsemi") (field (name "CONTRIBUTOR") "lcsc"))
      (libsource (lib "altium-import") (part "root_1_WS2812C-4020_"))
    )
    (comp (ref "LED44")
      (value "WS2812C-4020")
      (fields (field (name "MANUFACTURER") "worldsemi") (field (name "CONTRIBUTOR") "lcsc"))
      (libsource (lib "altium-import") (part "root_1_WS2812C-4020_"))
    )
    (comp (ref "LED45")
      (value "WS2812C-4020")
      (fields (field (name "MANUFACTURER") "worldsemi") (field (name "CONTRIBUTOR") "lcsc"))
      (libsource (lib "altium-import") (part "root_1_WS2812C-4020_"))
    )
    (comp (ref "LED46")
      (value "WS2812C-4020")
      (fields (field (name "MANUFACTURER") "worldsemi") (field (name "CONTRIBUTOR") "lcsc"))
      (libsource (lib "altium-import") (part "root_1_WS2812C-4020_"))
    )
    (comp (ref "LED47")
      (value "WS2812C-4020")
      (fields (field (name "MANUFACTURER") "worldsemi") (field (name "CONTRIBUTOR") "lcsc"))
      (libsource (lib "altium-import") (part "root_1_WS2812C-4020_"))
    )
    (comp (ref "LED48")
      (value "WS2812C-4020")
      (fields (field (name "MANUFACTURER") "worldsemi") (field (name "CONTRIBUTOR") "lcsc"))
      (libsource (lib "altium-import") (part "root_1_WS2812C-4020_"))
    )
    (comp (ref "LED49")
      (value "WS2812C-4020")
      (fields (field (name "MANUFACTURER") "worldsemi") (field (name "CONTRIBUTOR") "lcsc"))
      (libsource (lib "altium-import") (part "root_1_WS2812C-4020_"))
    )
    (comp (ref "LED50")
      (value "WS2812C-4020")
      (fields (field (name "MANUFACTURER") "worldsemi") (field (name "CONTRIBUTOR") "lcsc"))
      (libsource (lib "altium-import") (part "root_1_WS2812C-4020_"))
    )
    (comp (ref "LED51")
      (value "WS2812C-4020")
      (fields (field (name "MANUFACTURER") "worldsemi") (field (name "CONTRIBUTOR") "lcsc"))
      (libsource (lib "altium-import") (part "root_1_WS2812C-4020_"))
    )
    (comp (ref "LED52")
      (value "WS2812C-4020")
      (fields (field (name "MANUFACTURER") "worldsemi") (field (name "CONTRIBUTOR") "lcsc"))
      (libsource (lib "altium-import") (part "root_1_WS2812C-4020_"))
    )
    (comp (ref "LED53")
      (value "WS2812C-4020")
      (fields (field (name "MANUFACTURER") "worldsemi") (field (name "CONTRIBUTOR") "lcsc"))
      (libsource (lib "altium-import") (part "root_1_WS2812C-4020_"))
    )
    (comp (ref "LED54")
      (value "WS2812C-4020")
      (fields (field (name "MANUFACTURER") "worldsemi") (field (name "CONTRIBUTOR") "lcsc"))
      (libsource (lib "altium-import") (part "root_1_WS2812C-4020_"))
    )
    (comp (ref "LED55")
      (value "WS2812C-4020")
      (fields (field (name "MANUFACTURER") "worldsemi") (field (name "CONTRIBUTOR") "lcsc"))
      (libsource (lib "altium-import") (part "root_1_WS2812C-4020_"))
    )
    (comp (ref "LED56")
      (value "WS2812C-4020")
      (fields (field (name "MANUFACTURER") "worldsemi") (field (name "CONTRIBUTOR") "lcsc"))
      (libsource (lib "altium-import") (part "root_1_WS2812C-4020_"))
    )
    (comp (ref "LED57")
      (value "WS2812C-4020")
      (fields (field (name "MANUFACTURER") "worldsemi") (field (name "CONTRIBUTOR") "lcsc"))
      (libsource (lib "altium-import") (part "root_1_WS2812C-4020_"))
    )
    (comp (ref "LED58")
      (value "WS2812C-4020")
      (fields (field (name "MANUFACTURER") "worldsemi") (field (name "CONTRIBUTOR") "lcsc"))
      (libsource (lib "altium-import") (part "root_1_WS2812C-4020_"))
    )
    (comp (ref "LED59")
      (value "WS2812C-4020")
      (fields (field (name "MANUFACTURER") "worldsemi") (field (name "CONTRIBUTOR") "lcsc"))
      (libsource (lib "altium-import") (part "root_1_WS2812C-4020_"))
    )
    (comp (ref "LED60")
      (value "WS2812C-4020")
      (fields (field (name "MANUFACTURER") "worldsemi") (field (name "CONTRIBUTOR") "lcsc"))
      (libsource (lib "altium-import") (part "root_1_WS2812C-4020_"))
    )
    (comp (ref "LED61")
      (value "WS2812C-4020")
      (fields (field (name "MANUFACTURER") "worldsemi") (field (name "CONTRIBUTOR") "lcsc"))
      (libsource (lib "altium-import") (part "root_1_WS2812C-4020_"))
    )
    (comp (ref "LED62")
      (value "WS2812C-4020")
      (fields (field (name "MANUFACTURER") "worldsemi") (field (name "CONTRIBUTOR") "lcsc"))
      (libsource (lib "altium-import") (part "root_1_WS2812C-4020_"))
    )
    (comp (ref "LED63")
      (value "WS2812C-4020")
      (fields (field (name "MANUFACTURER") "worldsemi") (field (name "CONTRIBUTOR") "lcsc"))
      (libsource (lib "altium-import") (part "root_1_WS2812C-4020_"))
    )
    (comp (ref "LED64")
      (value "WS2812C-4020")
      (fields (field (name "MANUFACTURER") "worldsemi") (field (name "CONTRIBUTOR") "lcsc"))
      (libsource (lib "altium-import") (part "root_1_WS2812C-4020_"))
    )
    (comp (ref "LED65")
      (value "WS2812C-4020")
      (fields (field (name "MANUFACTURER") "worldsemi") (field (name "CONTRIBUTOR") "lcsc"))
      (libsource (lib "altium-import") (part "root_1_WS2812C-4020_"))
    )
    (comp (ref "LED66")
      (value "WS2812C-4020")
      (fields (field (name "MANUFACTURER") "worldsemi") (field (name "CONTRIBUTOR") "lcsc"))
      (libsource (lib "altium-import") (part "root_1_WS2812C-4020_"))
    )
    (comp (ref "LED67")
      (value "WS2812C-4020")
      (fields (field (name "MANUFACTURER") "worldsemi") (field (name "CONTRIBUTOR") "lcsc"))
      (libsource (lib "altium-import") (part "root_1_WS2812C-4020_"))
    )
    (comp (ref "LED68")
      (value "WS2812C-4020")
      (fields (field (name "MANUFACTURER") "worldsemi") (field (name "CONTRIBUTOR") "lcsc"))
      (libsource (lib "altium-import") (part "root_1_WS2812C-4020_"))
    )
    (comp (ref "LED69")
      (value "WS2812C-4020")
      (fields (field (name "MANUFACTURER") "worldsemi") (field (name "CONTRIBUTOR") "lcsc"))
      (libsource (lib "altium-import") (part "root_1_WS2812C-4020_"))
    )
    (comp (ref "LED70")
      (value "WS2812C-4020")
      (fields (field (name "MANUFACTURER") "worldsemi") (field (name "CONTRIBUTOR") "lcsc"))
      (libsource (lib "altium-import") (part "root_1_WS2812C-4020_"))
    )
    (comp (ref "LED71")
      (value "WS2812C-4020")
      (fields (field (name "MANUFACTURER") "worldsemi") (field (name "CONTRIBUTOR") "lcsc"))
      (libsource (lib "altium-import") (part "root_1_WS2812C-4020_"))
    )
    (comp (ref "LED72")
      (value "WS2812C-4020")
      (fields (field (name "MANUFACTURER") "worldsemi") (field (name "CONTRIBUTOR") "lcsc"))
      (libsource (lib "altium-import") (part "root_1_WS2812C-4020_"))
    )
    (comp (ref "LED73")
      (value "WS2812C-4020")
      (fields (field (name "MANUFACTURER") "worldsemi") (field (name "CONTRIBUTOR") "lcsc"))
      (libsource (lib "altium-import") (part "root_1_WS2812C-4020_"))
    )
    (comp (ref "LED74")
      (value "WS2812C-4020")
      (fields (field (name "MANUFACTURER") "worldsemi") (field (name "CONTRIBUTOR") "lcsc"))
      (libsource (lib "altium-import") (part "root_1_WS2812C-4020_"))
    )
    (comp (ref "LED75")
      (value "WS2812C-4020")
      (fields (field (name "MANUFACTURER") "worldsemi") (field (name "CONTRIBUTOR") "lcsc"))
      (libsource (lib "altium-import") (part "root_1_WS2812C-4020_"))
    )
    (comp (ref "LED76")
      (value "WS2812C-4020")
      (fields (field (name "MANUFACTURER") "worldsemi") (field (name "CONTRIBUTOR") "lcsc"))
      (libsource (lib "altium-import") (part "root_1_WS2812C-4020_"))
    )
    (comp (ref "LED77")
      (value "WS2812C-4020")
      (fields (field (name "MANUFACTURER") "worldsemi") (field (name "CONTRIBUTOR") "lcsc"))
      (libsource (lib "altium-import") (part "root_1_WS2812C-4020_"))
    )
    (comp (ref "LED78")
      (value "WS2812C-4020")
      (fields (field (name "MANUFACTURER") "worldsemi") (field (name "CONTRIBUTOR") "lcsc"))
      (libsource (lib "altium-import") (part "root_1_WS2812C-4020_"))
    )
    (comp (ref "P1")
      (value "CONN-TH_2P-P5.08")
      (fields (field (name "CONTRIBUTOR") "LCEDA_Lib"))
      (libsource (lib "") (part "root_2_CONN-TH_2P-P5.08__2"))
    )
    (comp (ref "P2")
      (value "CONN-TH_2P-P5.08")
      (fields (field (name "CONTRIBUTOR") "LCEDA_Lib"))
      (libsource (lib "altium-import") (part "root_2_CONN-TH_2P-P5.08_"))
    )
    (comp (ref "P3")
      (value "CONN-TH_2P-P5.08")
      (fields (field (name "CONTRIBUTOR") "LCEDA_Lib"))
      (libsource (lib "altium-import") (part "root_2_CONN-TH_2P-P5.08_"))
    )
    (comp (ref "P4")
      (value "CONN-TH_2P-P5.08")
      (fields (field (name "CONTRIBUTOR") "LCEDA_Lib"))
      (libsource (lib "") (part "root_2_CONN-TH_2P-P5.08__1"))
    )
    (comp (ref "P5")
      (value "CONN-TH_2P-P5.08")
      (fields (field (name "CONTRIBUTOR") "LCEDA_Lib"))
      (libsource (lib "") (part "root_2_CONN-TH_2P-P5.08__1"))
    )
    (comp (ref "R1")
      (value "100kΩ")
      (fields
        (field (name "MANUFACTURER") "UNI-ROYAL(厚声)")
        (field (name "MANUFACTURER PART") "0603WAF1003T5E")
      )
      (libsource (lib "altium-import") (part "root_1_100kΩ_"))
    )
    (comp (ref "R2")
      (value "13kΩ")
      (fields
        (field (name "MANUFACTURER") "UNI-ROYAL(厚声)")
        (field (name "MANUFACTURER PART") "0603WAF1302T5E")
      )
      (libsource (lib "altium-import") (part "root_1_13kΩ_"))
    )
    (comp (ref "R3")
      (value "1.3kΩ")
      (fields
        (field (name "MANUFACTURER") "UNI-ROYAL(厚声)")
        (field (name "MANUFACTURER PART") "0603WAF1301T5E")
      )
      (libsource (lib "altium-import") (part "root_0_1.3kΩ_"))
    )
    (comp (ref "R4")
      (value "1.3kΩ")
      (fields
        (field (name "MANUFACTURER") "UNI-ROYAL(厚声)")
        (field (name "MANUFACTURER PART") "0603WAF1301T5E")
      )
      (libsource (lib "altium-import") (part "root_0_1.3kΩ_"))
    )
    (comp (ref "R5")
      (value "9.1kΩ")
      (fields
        (field (name "MANUFACTURER") "UNI-ROYAL(厚声)")
        (field (name "MANUFACTURER PART") "0603WAF9101T5E")
      )
      (libsource (lib "altium-import") (part "root_0_9.1kΩ_"))
    )
    (comp (ref "R6")
      (value "9.1kΩ")
      (fields
        (field (name "MANUFACTURER") "UNI-ROYAL(厚声)")
        (field (name "MANUFACTURER PART") "0603WAF9101T5E")
      )
      (libsource (lib "altium-import") (part "root_0_9.1kΩ_"))
    )
    (comp (ref "R7")
      (value "10kΩ")
      (fields
        (field (name "MANUFACTURER") "UNI-ROYAL(厚声)")
        (field (name "MANUFACTURER PART") "0603WAF1002T5E")
      )
      (libsource (lib "altium-import") (part "root_0_10kΩ_"))
    )
    (comp (ref "R8")
      (value "10kΩ")
      (fields
        (field (name "MANUFACTURER") "UNI-ROYAL(厚声)")
        (field (name "MANUFACTURER PART") "0603WAF1002T5E")
      )
      (libsource (lib "altium-import") (part "root_0_10kΩ_"))
    )
    (comp (ref "R9")
      (value "1.8kΩ")
      (fields
        (field (name "MANUFACTURER") "UNI-ROYAL(厚声)")
        (field (name "MANUFACTURER PART") "0603WAF1801T5E")
      )
      (libsource (lib "altium-import") (part "root_1_1.8kΩ_"))
    )
    (comp (ref "R10")
      (value "1.8kΩ")
      (fields
        (field (name "MANUFACTURER") "UNI-ROYAL(厚声)")
        (field (name "MANUFACTURER PART") "0603WAF1801T5E")
      )
      (libsource (lib "altium-import") (part "root_1_1.8kΩ_"))
    )
    (comp (ref "R11")
      (value "100kΩ")
      (fields
        (field (name "MANUFACTURER") "UNI-ROYAL(厚声)")
        (field (name "MANUFACTURER PART") "0603WAF1003T5E")
      )
      (libsource (lib "altium-import") (part "root_1_100kΩ_"))
    )
    (comp (ref "R12")
      (value "100kΩ")
      (fields
        (field (name "MANUFACTURER") "UNI-ROYAL(厚声)")
        (field (name "MANUFACTURER PART") "0603WAF1003T5E")
      )
      (libsource (lib "altium-import") (part "root_1_100kΩ_"))
    )
    (comp (ref "R13")
      (value "100kΩ")
      (fields
        (field (name "MANUFACTURER") "UNI-ROYAL(厚声)")
        (field (name "MANUFACTURER PART") "0603WAF1003T5E")
      )
      (libsource (lib "altium-import") (part "root_1_100kΩ_"))
    )
    (comp (ref "R14")
      (value "100kΩ")
      (fields
        (field (name "MANUFACTURER") "UNI-ROYAL(厚声)")
        (field (name "MANUFACTURER PART") "0603WAF1003T5E")
      )
      (libsource (lib "altium-import") (part "root_1_100kΩ_"))
    )
    (comp (ref "SW1")
      (value "SKRPACE010")
      (fields (field (name "MANUFACTURER") "ALPSALPINE(阿尔卑斯阿尔派)") (field (name "CONTRIBUTOR") "LCSC"))
      (libsource (lib "altium-import") (part "root_0_SKRPACE010_"))
    )
    (comp (ref "U1")
      (value "TPS54202DDCR")
      (fields (field (name "MANUFACTURER") "TI(德州仪器)") (field (name "CONTRIBUTOR") "LCSC"))
      (libsource (lib "altium-import") (part "root_0_TPS54202DDCR_"))
    )
    (comp (ref "U2")
      (value "RP2040-ZERO")
      (fields
        (field (name "MANUFACTURER") "Waveshare(微雪电子)")
        (field (name "MANUFACTURER PART") "RP2040-Zero")
        (field (name "CONTRIBUTOR") "lcsc")
      )
      (libsource (lib "altium-import") (part "root_0_RP2040-ZERO_"))
    )
  )
  (nets
    (net (code "1") (name "+5V") (class "Default")
      (node (ref "C10") (pin "2") (pinfunction "2_2") (pintype "passive"))
      (node (ref "C11") (pin "2") (pinfunction "2_2") (pintype "passive"))
      (node (ref "C12") (pin "2") (pinfunction "2_2") (pintype "passive"))
      (node (ref "C13") (pin "2") (pinfunction "2_2") (pintype "passive"))
      (node (ref "C14") (pin "2") (pinfunction "2_2") (pintype "passive"))
      (node (ref "C15") (pin "2") (pinfunction "2_2") (pintype "passive"))
      (node (ref "C16") (pin "2") (pinfunction "2_2") (pintype "passive"))
      (node (ref "C17") (pin "2") (pinfunction "2_2") (pintype "passive"))
      (node (ref "C18") (pin "2") (pinfunction "2_2") (pintype "passive"))
      (node (ref "C19") (pin "2") (pinfunction "2_2") (pintype "passive"))
      (node (ref "C20") (pin "2") (pinfunction "2_2") (pintype "passive"))
      (node (ref "C21") (pin "2") (pinfunction "2_2") (pintype "passive"))
      (node (ref "C22") (pin "2") (pinfunction "2_2") (pintype "passive"))
      (node (ref "C23") (pin "2") (pinfunction "2_2") (pintype "passive"))
      (node (ref "C24") (pin "2") (pinfunction "2_2") (pintype "passive"))
      (node (ref "C25") (pin "2") (pinfunction "2_2") (pintype "passive"))
      (node (ref "C26") (pin "2") (pinfunction "2_2") (pintype "passive"))
      (node (ref "C27") (pin "2") (pinfunction "2_2") (pintype "passive"))
      (node (ref "C28") (pin "2") (pinfunction "2_2") (pintype "passive"))
      (node (ref "C29") (pin "2") (pinfunction "2_2") (pintype "passive"))
      (node (ref "C30") (pin "2") (pinfunction "2_2") (pintype "passive"))
      (node (ref "C31") (pin "2") (pinfunction "2_2") (pintype "passive"))
      (node (ref "C32") (pin "2") (pinfunction "2_2") (pintype "passive"))
      (node (ref "C33") (pin "2") (pinfunction "2_2") (pintype "passive"))
      (node (ref "C34") (pin "2") (pinfunction "2_2") (pintype "passive"))
      (node (ref "C35") (pin "2") (pinfunction "2_2") (pintype "passive"))
      (node (ref "C36") (pin "2") (pinfunction "2_2") (pintype "passive"))
      (node (ref "C37") (pin "2") (pinfunction "2_2") (pintype "passive"))
      (node (ref "C38") (pin "2") (pinfunction "2_2") (pintype "passive"))
      (node (ref "C39") (pin "2") (pinfunction "2_2") (pintype "passive"))
      (node (ref "C40") (pin "2") (pinfunction "2_2") (pintype "passive"))
      (node (ref "C41") (pin "2") (pinfunction "2_2") (pintype "passive"))
      (node (ref "C42") (pin "2") (pinfunction "2_2") (pintype "passive"))
      (node (ref "C43") (pin "2") (pinfunction "2_2") (pintype "passive"))
      (node (ref "C44") (pin "2") (pinfunction "2_2") (pintype "passive"))
      (node (ref "C51") (pin "2") (pinfunction "2_2") (pintype "passive"))
      (node (ref "C52") (pin "2") (pinfunction "2_2") (pintype "passive"))
      (node (ref "C53") (pin "2") (pinfunction "2_2") (pintype "passive"))
      (node (ref "C54") (pin "2") (pinfunction "2_2") (pintype "passive"))
      (node (ref "C55") (pin "2") (pinfunction "2_2") (pintype "passive"))
      (node (ref "C56") (pin "2") (pinfunction "2_2") (pintype "passive"))
      (node (ref "C57") (pin "2") (pinfunction "2_2") (pintype "passive"))
      (node (ref "C58") (pin "2") (pinfunction "2_2") (pintype "passive"))
      (node (ref "C59") (pin "2") (pinfunction "2_2") (pintype "passive"))
      (node (ref "C6") (pin "2") (pinfunction "2_2") (pintype "passive"))
      (node (ref "C60") (pin "2") (pinfunction "2_2") (pintype "passive"))
      (node (ref "C61") (pin "2") (pinfunction "2_2") (pintype "passive"))
      (node (ref "C62") (pin "2") (pinfunction "2_2") (pintype "passive"))
      (node (ref "C63") (pin "2") (pinfunction "2_2") (pintype "passive"))
      (node (ref "C64") (pin "2") (pinfunction "2_2") (pintype "passive"))
      (node (ref "C65") (pin "2") (pinfunction "2_2") (pintype "passive"))
      (node (ref "C66") (pin "2") (pinfunction "2_2") (pintype "passive"))
      (node (ref "C67") (pin "2") (pinfunction "2_2") (pintype "passive"))
      (node (ref "C68") (pin "2") (pinfunction "2_2") (pintype "passive"))
      (node (ref "C69") (pin "2") (pinfunction "2_2") (pintype "passive"))
      (node (ref "C70") (pin "2") (pinfunction "2_2") (pintype "passive"))
      (node (ref "C71") (pin "2") (pinfunction "2_2") (pintype "passive"))
      (node (ref "C72") (pin "2") (pinfunction "2_2") (pintype "passive"))
      (node (ref "C73") (pin "2") (pinfunction "2_2") (pintype "passive"))
      (node (ref "C74") (pin "2") (pinfunction "2_2") (pintype "passive"))
      (node (ref "C75") (pin "2") (pinfunction "2_2") (pintype "passive"))
      (node (ref "C76") (pin "2") (pinfunction "2_2") (pintype "passive"))
      (node (ref "C77") (pin "2") (pinfunction "2_2") (pintype "passive"))
      (node (ref "C78") (pin "2") (pinfunction "2_2") (pintype "passive"))
      (node (ref "C79") (pin "2") (pinfunction "2_2") (pintype "passive"))
      (node (ref "C80") (pin "2") (pinfunction "2_2") (pintype "passive"))
      (node (ref "C81") (pin "2") (pinfunction "2_2") (pintype "passive"))
      (node (ref "C82") (pin "2") (pinfunction "2_2") (pintype "passive"))
      (node (ref "C83") (pin "2") (pinfunction "2_2") (pintype "passive"))
      (node (ref "C84") (pin "2") (pinfunction "2_2") (pintype "passive"))
      (node (ref "C85") (pin "2") (pinfunction "2_2") (pintype "passive"))
      (node (ref "C9") (pin "2") (pinfunction "2_2") (pintype "passive"))
      (node (ref "D2") (pin "1") (pinfunction "K_1") (pintype "passive"))
      (node (ref "LED1") (pin "2") (pinfunction "VDD_2") (pintype "passive"))
      (node (ref "LED10") (pin "2") (pinfunction "VDD_2") (pintype "passive"))
      (node (ref "LED11") (pin "2") (pinfunction "VDD_2") (pintype "passive"))
      (node (ref "LED12") (pin "2") (pinfunction "VDD_2") (pintype "passive"))
      (node (ref "LED13") (pin "2") (pinfunction "VDD_2") (pintype "passive"))
      (node (ref "LED14") (pin "2") (pinfunction "VDD_2") (pintype "passive"))
      (node (ref "LED15") (pin "2") (pinfunction "VDD_2") (pintype "passive"))
      (node (ref "LED16") (pin "2") (pinfunction "VDD_2") (pintype "passive"))
      (node (ref "LED17") (pin "2") (pinfunction "VDD_2") (pintype "passive"))
      (node (ref "LED18") (pin "2") (pinfunction "VDD_2") (pintype "passive"))
      (node (ref "LED19") (pin "2") (pinfunction "VDD_2") (pintype "passive"))
      (node (ref "LED2") (pin "2") (pinfunction "VDD_2") (pintype "passive"))
      (node (ref "LED20") (pin "2") (pinfunction "VDD_2") (pintype "passive"))
      (node (ref "LED21") (pin "2") (pinfunction "VDD_2") (pintype "passive"))
      (node (ref "LED22") (pin "2") (pinfunction "VDD_2") (pintype "passive"))
      (node (ref "LED23") (pin "2") (pinfunction "VDD_2") (pintype "passive"))
      (node (ref "LED24") (pin "2") (pinfunction "VDD_2") (pintype "passive"))
      (node (ref "LED25") (pin "2") (pinfunction "VDD_2") (pintype "passive"))
      (node (ref "LED26") (pin "2") (pinfunction "VDD_2") (pintype "passive"))
      (node (ref "LED27") (pin "2") (pinfunction "VDD_2") (pintype "passive"))
      (node (ref "LED28") (pin "2") (pinfunction "VDD_2") (pintype "passive"))
      (node (ref "LED29") (pin "2") (pinfunction "VDD_2") (pintype "passive"))
      (node (ref "LED3") (pin "2") (pinfunction "VDD_2") (pintype "passive"))
      (node (ref "LED30") (pin "2") (pinfunction "VDD_2") (pintype "passive"))
      (node (ref "LED31") (pin "2") (pinfunction "VDD_2") (pintype "passive"))
      (node (ref "LED32") (pin "2") (pinfunction "VDD_2") (pintype "passive"))
      (node (ref "LED33") (pin "2") (pinfunction "VDD_2") (pintype "passive"))
      (node (ref "LED34") (pin "2") (pinfunction "VDD_2") (pintype "passive"))
      (node (ref "LED35") (pin "2") (pinfunction "VDD_2") (pintype "passive"))
      (node (ref "LED36") (pin "2") (pinfunction "VDD_2") (pintype "passive"))
      (node (ref "LED4") (pin "2") (pinfunction "VDD_2") (pintype "passive"))
      (node (ref "LED43") (pin "2") (pinfunction "VDD_2") (pintype "passive"))
      (node (ref "LED44") (pin "2") (pinfunction "VDD_2") (pintype "passive"))
      (node (ref "LED45") (pin "2") (pinfunction "VDD_2") (pintype "passive"))
      (node (ref "LED46") (pin "2") (pinfunction "VDD_2") (pintype "passive"))
      (node (ref "LED47") (pin "2") (pinfunction "VDD_2") (pintype "passive"))
      (node (ref "LED48") (pin "2") (pinfunction "VDD_2") (pintype "passive"))
      (node (ref "LED49") (pin "2") (pinfunction "VDD_2") (pintype "passive"))
      (node (ref "LED5") (pin "2") (pinfunction "VDD_2") (pintype "passive"))
      (node (ref "LED50") (pin "2") (pinfunction "VDD_2") (pintype "passive"))
      (node (ref "LED51") (pin "2") (pinfunction "VDD_2") (pintype "passive"))
      (node (ref "LED52") (pin "2") (pinfunction "VDD_2") (pintype "passive"))
      (node (ref "LED53") (pin "2") (pinfunction "VDD_2") (pintype "passive"))
      (node (ref "LED54") (pin "2") (pinfunction "VDD_2") (pintype "passive"))
      (node (ref "LED55") (pin "2") (pinfunction "VDD_2") (pintype "passive"))
      (node (ref "LED56") (pin "2") (pinfunction "VDD_2") (pintype "passive"))
      (node (ref "LED57") (pin "2") (pinfunction "VDD_2") (pintype "passive"))
      (node (ref "LED58") (pin "2") (pinfunction "VDD_2") (pintype "passive"))
      (node (ref "LED59") (pin "2") (pinfunction "VDD_2") (pintype "passive"))
      (node (ref "LED6") (pin "2") (pinfunction "VDD_2") (pintype "passive"))
      (node (ref "LED60") (pin "2") (pinfunction "VDD_2") (pintype "passive"))
      (node (ref "LED61") (pin "2") (pinfunction "VDD_2") (pintype "passive"))
      (node (ref "LED62") (pin "2") (pinfunction "VDD_2") (pintype "passive"))
      (node (ref "LED63") (pin "2") (pinfunction "VDD_2") (pintype "passive"))
      (node (ref "LED64") (pin "2") (pinfunction "VDD_2") (pintype "passive"))
      (node (ref "LED65") (pin "2") (pinfunction "VDD_2") (pintype "passive"))
      (node (ref "LED66") (pin "2") (pinfunction "VDD_2") (pintype "passive"))
      (node (ref "LED67") (pin "2") (pinfunction "VDD_2") (pintype "passive"))
      (node (ref "LED68") (pin "2") (pinfunction "VDD_2") (pintype "passive"))
      (node (ref "LED69") (pin "2") (pinfunction "VDD_2") (pintype "passive"))
      (node (ref "LED7") (pin "2") (pinfunction "VDD_2") (pintype "passive"))
      (node (ref "LED70") (pin "2") (pinfunction "VDD_2") (pintype "passive"))
      (node (ref "LED71") (pin "2") (pinfunction "VDD_2") (pintype "passive"))
      (node (ref "LED72") (pin "2") (pinfunction "VDD_2") (pintype "passive"))
      (node (ref "LED73") (pin "2") (pinfunction "VDD_2") (pintype "passive"))
      (node (ref "LED74") (pin "2") (pinfunction "VDD_2") (pintype "passive"))
      (node (ref "LED75") (pin "2") (pinfunction "VDD_2") (pintype "passive"))
      (node (ref "LED76") (pin "2") (pinfunction "VDD_2") (pintype "passive"))
      (node (ref "LED77") (pin "2") (pinfunction "VDD_2") (pintype "passive"))
      (node (ref "LED78") (pin "2") (pinfunction "VDD_2") (pintype "passive"))
      (node (ref "LED8") (pin "2") (pinfunction "VDD_2") (pintype "passive"))
      (node (ref "LED9") (pin "2") (pinfunction "VDD_2") (pintype "passive"))
      (node (ref "U2") (pin "23") (pinfunction "5V_23") (pintype "passive"))
    )
    (net (code "2") (name "/3V3") (class "Default")
      (node (ref "R11") (pin "2") (pinfunction "2_2") (pintype "passive"))
      (node (ref "R13") (pin "2") (pinfunction "2_2") (pintype "passive"))
      (node (ref "U2") (pin "21") (pinfunction "3V3_21") (pintype "passive"))
    )
    (net (code "3") (name "/LEFT") (class "Default")
      (node (ref "LED1") (pin "1") (pinfunction "DIN_1") (pintype "passive"))
      (node (ref "U2") (pin "15") (pinfunction "GP14_15") (pintype "passive"))
    )
    (net (code "4") (name "/RIGHT") (class "Default")
      (node (ref "LED43") (pin "1") (pinfunction "DIN_1") (pintype "passive"))
      (node (ref "U2") (pin "16") (pinfunction "GP15_16") (pintype "passive"))
    )
    (net (code "5") (name "GND") (class "Default")
      (node (ref "C1") (pin "1") (pinfunction "1_1") (pintype "passive"))
      (node (ref "C10") (pin "1") (pinfunction "1_1") (pintype "passive"))
      (node (ref "C11") (pin "1") (pinfunction "1_1") (pintype "passive"))
      (node (ref "C12") (pin "1") (pinfunction "1_1") (pintype "passive"))
      (node (ref "C13") (pin "1") (pinfunction "1_1") (pintype "passive"))
      (node (ref "C14") (pin "1") (pinfunction "1_1") (pintype "passive"))
      (node (ref "C15") (pin "1") (pinfunction "1_1") (pintype "passive"))
      (node (ref "C16") (pin "1") (pinfunction "1_1") (pintype "passive"))
      (node (ref "C17") (pin "1") (pinfunction "1_1") (pintype "passive"))
      (node (ref "C18") (pin "1") (pinfunction "1_1") (pintype "passive"))
      (node (ref "C19") (pin "1") (pinfunction "1_1") (pintype "passive"))
      (node (ref "C20") (pin "1") (pinfunction "1_1") (pintype "passive"))
      (node (ref "C21") (pin "1") (pinfunction "1_1") (pintype "passive"))
      (node (ref "C22") (pin "1") (pinfunction "1_1") (pintype "passive"))
      (node (ref "C23") (pin "1") (pinfunction "1_1") (pintype "passive"))
      (node (ref "C24") (pin "1") (pinfunction "1_1") (pintype "passive"))
      (node (ref "C25") (pin "1") (pinfunction "1_1") (pintype "passive"))
      (node (ref "C26") (pin "1") (pinfunction "1_1") (pintype "passive"))
      (node (ref "C27") (pin "1") (pinfunction "1_1") (pintype "passive"))
      (node (ref "C28") (pin "1") (pinfunction "1_1") (pintype "passive"))
      (node (ref "C29") (pin "1") (pinfunction "1_1") (pintype "passive"))
      (node (ref "C30") (pin "1") (pinfunction "1_1") (pintype "passive"))
      (node (ref "C31") (pin "1") (pinfunction "1_1") (pintype "passive"))
      (node (ref "C32") (pin "1") (pinfunction "1_1") (pintype "passive"))
      (node (ref "C33") (pin "1") (pinfunction "1_1") (pintype "passive"))
      (node (ref "C34") (pin "1") (pinfunction "1_1") (pintype "passive"))
      (node (ref "C35") (pin "1") (pinfunction "1_1") (pintype "passive"))
      (node (ref "C36") (pin "1") (pinfunction "1_1") (pintype "passive"))
      (node (ref "C37") (pin "1") (pinfunction "1_1") (pintype "passive"))
      (node (ref "C38") (pin "1") (pinfunction "1_1") (pintype "passive"))
      (node (ref "C39") (pin "1") (pinfunction "1_1") (pintype "passive"))
      (node (ref "C4") (pin "1") (pinfunction "1_1") (pintype "passive"))
      (node (ref "C40") (pin "1") (pinfunction "1_1") (pintype "passive"))
      (node (ref "C41") (pin "1") (pinfunction "1_1") (pintype "passive"))
      (node (ref "C42") (pin "1") (pinfunction "1_1") (pintype "passive"))
      (node (ref "C43") (pin "1") (pinfunction "1_1") (pintype "passive"))
      (node (ref "C44") (pin "1") (pinfunction "1_1") (pintype "passive"))
      (node (ref "C47") (pin "1") (pinfunction "1_1") (pintype "passive"))
      (node (ref "C48") (pin "1") (pinfunction "1_1") (pintype "passive"))
      (node (ref "C49") (pin "2") (pinfunction "2_2") (pintype "passive"))
      (node (ref "C5") (pin "1") (pinfunction "1_1") (pintype "passive"))
      (node (ref "C50") (pin "2") (pinfunction "2_2") (pintype "passive"))
      (node (ref "C51") (pin "1") (pinfunction "1_1") (pintype "passive"))
      (node (ref "C52") (pin "1") (pinfunction "1_1") (pintype "passive"))
      (node (ref "C53") (pin "1") (pinfunction "1_1") (pintype "passive"))
      (node (ref "C54") (pin "1") (pinfunction "1_1") (pintype "passive"))
      (node (ref "C55") (pin "1") (pinfunction "1_1") (pintype "passive"))
      (node (ref "C56") (pin "1") (pinfunction "1_1") (pintype "passive"))
      (node (ref "C57") (pin "1") (pinfunction "1_1") (pintype "passive"))
      (node (ref "C58") (pin "1") (pinfunction "1_1") (pintype "passive"))
      (node (ref "C59") (pin "1") (pinfunction "1_1") (pintype "passive"))
      (node (ref "C6") (pin "1") (pinfunction "1_1") (pintype "passive"))
      (node (ref "C60") (pin "1") (pinfunction "1_1") (pintype "passive"))
      (node (ref "C61") (pin "1") (pinfunction "1_1") (pintype "passive"))
      (node (ref "C62") (pin "1") (pinfunction "1_1") (pintype "passive"))
      (node (ref "C63") (pin "1") (pinfunction "1_1") (pintype "passive"))
      (node (ref "C64") (pin "1") (pinfunction "1_1") (pintype "passive"))
      (node (ref "C65") (pin "1") (pinfunction "1_1") (pintype "passive"))
      (node (ref "C66") (pin "1") (pinfunction "1_1") (pintype "passive"))
      (node (ref "C67") (pin "1") (pinfunction "1_1") (pintype "passive"))
      (node (ref "C68") (pin "1") (pinfunction "1_1") (pintype "passive"))
      (node (ref "C69") (pin "1") (pinfunction "1_1") (pintype "passive"))
      (node (ref "C7") (pin "1") (pinfunction "1_1") (pintype "passive"))
      (node (ref "C70") (pin "1") (pinfunction "1_1") (pintype "passive"))
      (node (ref "C71") (pin "1") (pinfunction "1_1") (pintype "passive"))
      (node (ref "C72") (pin "1") (pinfunction "1_1") (pintype "passive"))
      (node (ref "C73") (pin "1") (pinfunction "1_1") (pintype "passive"))
      (node (ref "C74") (pin "1") (pinfunction "1_1") (pintype "passive"))
      (node (ref "C75") (pin "1") (pinfunction "1_1") (pintype "passive"))
      (node (ref "C76") (pin "1") (pinfunction "1_1") (pintype "passive"))
      (node (ref "C77") (pin "1") (pinfunction "1_1") (pintype "passive"))
      (node (ref "C78") (pin "1") (pinfunction "1_1") (pintype "passive"))
      (node (ref "C79") (pin "1") (pinfunction "1_1") (pintype "passive"))
      (node (ref "C8") (pin "1") (pinfunction "1_1") (pintype "passive"))
      (node (ref "C80") (pin "1") (pinfunction "1_1") (pintype "passive"))
      (node (ref "C81") (pin "1") (pinfunction "1_1") (pintype "passive"))
      (node (ref "C82") (pin "1") (pinfunction "1_1") (pintype "passive"))
      (node (ref "C83") (pin "1") (pinfunction "1_1") (pintype "passive"))
      (node (ref "C84") (pin "1") (pinfunction "1_1") (pintype "passive"))
      (node (ref "C85") (pin "1") (pinfunction "1_1") (pintype "passive"))
      (node (ref "C9") (pin "1") (pinfunction "1_1") (pintype "passive"))
      (node (ref "LED1") (pin "4") (pinfunction "VSS_4") (pintype "passive"))
      (node (ref "LED10") (pin "4") (pinfunction "VSS_4") (pintype "passive"))
      (node (ref "LED11") (pin "4") (pinfunction "VSS_4") (pintype "passive"))
      (node (ref "LED12") (pin "4") (pinfunction "VSS_4") (pintype "passive"))
      (node (ref "LED13") (pin "4") (pinfunction "VSS_4") (pintype "passive"))
      (node (ref "LED14") (pin "4") (pinfunction "VSS_4") (pintype "passive"))
      (node (ref "LED15") (pin "4") (pinfunction "VSS_4") (pintype "passive"))
      (node (ref "LED16") (pin "4") (pinfunction "VSS_4") (pintype "passive"))
      (node (ref "LED17") (pin "4") (pinfunction "VSS_4") (pintype "passive"))
      (node (ref "LED18") (pin "4") (pinfunction "VSS_4") (pintype "passive"))
      (node (ref "LED19") (pin "4") (pinfunction "VSS_4") (pintype "passive"))
      (node (ref "LED2") (pin "4") (pinfunction "VSS_4") (pintype "passive"))
      (node (ref "LED20") (pin "4") (pinfunction "VSS_4") (pintype "passive"))
      (node (ref "LED21") (pin "4") (pinfunction "VSS_4") (pintype "passive"))
      (node (ref "LED22") (pin "4") (pinfunction "VSS_4") (pintype "passive"))
      (node (ref "LED23") (pin "4") (pinfunction "VSS_4") (pintype "passive"))
      (node (ref "LED24") (pin "4") (pinfunction "VSS_4") (pintype "passive"))
      (node (ref "LED25") (pin "4") (pinfunction "VSS_4") (pintype "passive"))
      (node (ref "LED26") (pin "4") (pinfunction "VSS_4") (pintype "passive"))
      (node (ref "LED27") (pin "4") (pinfunction "VSS_4") (pintype "passive"))
      (node (ref "LED28") (pin "4") (pinfunction "VSS_4") (pintype "passive"))
      (node (ref "LED29") (pin "4") (pinfunction "VSS_4") (pintype "passive"))
      (node (ref "LED3") (pin "4") (pinfunction "VSS_4") (pintype "passive"))
      (node (ref "LED30") (pin "4") (pinfunction "VSS_4") (pintype "passive"))
      (node (ref "LED31") (pin "4") (pinfunction "VSS_4") (pintype "passive"))
      (node (ref "LED32") (pin "4") (pinfunction "VSS_4") (pintype "passive"))
      (node (ref "LED33") (pin "4") (pinfunction "VSS_4") (pintype "passive"))
      (node (ref "LED34") (pin "4") (pinfunction "VSS_4") (pintype "passive"))
      (node (ref "LED35") (pin "4") (pinfunction "VSS_4") (pintype "passive"))
      (node (ref "LED36") (pin "4") (pinfunction "VSS_4") (pintype "passive"))
      (node (ref "LED4") (pin "4") (pinfunction "VSS_4") (pintype "passive"))
      (node (ref "LED43") (pin "4") (pinfunction "VSS_4") (pintype "passive"))
      (node (ref "LED44") (pin "4") (pinfunction "VSS_4") (pintype "passive"))
      (node (ref "LED45") (pin "4") (pinfunction "VSS_4") (pintype "passive"))
      (node (ref "LED46") (pin "4") (pinfunction "VSS_4") (pintype "passive"))
      (node (ref "LED47") (pin "4") (pinfunction "VSS_4") (pintype "passive"))
      (node (ref "LED48") (pin "4") (pinfunction "VSS_4") (pintype "passive"))
      (node (ref "LED49") (pin "4") (pinfunction "VSS_4") (pintype "passive"))
      (node (ref "LED5") (pin "4") (pinfunction "VSS_4") (pintype "passive"))
      (node (ref "LED50") (pin "4") (pinfunction "VSS_4") (pintype "passive"))
      (node (ref "LED51") (pin "4") (pinfunction "VSS_4") (pintype "passive"))
      (node (ref "LED52") (pin "4") (pinfunction "VSS_4") (pintype "passive"))
      (node (ref "LED53") (pin "4") (pinfunction "VSS_4") (pintype "passive"))
      (node (ref "LED54") (pin "4") (pinfunction "VSS_4") (pintype "passive"))
      (node (ref "LED55") (pin "4") (pinfunction "VSS_4") (pintype "passive"))
      (node (ref "LED56") (pin "4") (pinfunction "VSS_4") (pintype "passive"))
      (node (ref "LED57") (pin "4") (pinfunction "VSS_4") (pintype "passive"))
      (node (ref "LED58") (pin "4") (pinfunction "VSS_4") (pintype "passive"))
      (node (ref "LED59") (pin "4") (pinfunction "VSS_4") (pintype "passive"))
      (node (ref "LED6") (pin "4") (pinfunction "VSS_4") (pintype "passive"))
      (node (ref "LED60") (pin "4") (pinfunction "VSS_4") (pintype "passive"))
      (node (ref "LED61") (pin "4") (pinfunction "VSS_4") (pintype "passive"))
      (node (ref "LED62") (pin "4") (pinfunction "VSS_4") (pintype "passive"))
      (node (ref "LED63") (pin "4") (pinfunction "VSS_4") (pintype "passive"))
      (node (ref "LED64") (pin "4") (pinfunction "VSS_4") (pintype "passive"))
      (node (ref "LED65") (pin "4") (pinfunction "VSS_4") (pintype "passive"))
      (node (ref "LED66") (pin "4") (pinfunction "VSS_4") (pintype "passive"))
      (node (ref "LED67") (pin "4") (pinfunction "VSS_4") (pintype "passive"))
      (node (ref "LED68") (pin "4") (pinfunction "VSS_4") (pintype "passive"))
      (node (ref "LED69") (pin "4") (pinfunction "VSS_4") (pintype "passive"))
      (node (ref "LED7") (pin "4") (pinfunction "VSS_4") (pintype "passive"))
      (node (ref "LED70") (pin "4") (pinfunction "VSS_4") (pintype "passive"))
      (node (ref "LED71") (pin "4") (pinfunction "VSS_4") (pintype "passive"))
      (node (ref "LED72") (pin "4") (pinfunction "VSS_4") (pintype "passive"))
      (node (ref "LED73") (pin "4") (pinfunction "VSS_4") (pintype "passive"))
      (node (ref "LED74") (pin "4") (pinfunction "VSS_4") (pintype "passive"))
      (node (ref "LED75") (pin "4") (pinfunction "VSS_4") (pintype "passive"))
      (node (ref "LED76") (pin "4") (pinfunction "VSS_4") (pintype "passive"))
      (node (ref "LED77") (pin "4") (pinfunction "VSS_4") (pintype "passive"))
      (node (ref "LED78") (pin "4") (pinfunction "VSS_4") (pintype "passive"))
      (node (ref "LED8") (pin "4") (pinfunction "VSS_4") (pintype "passive"))
      (node (ref "LED9") (pin "4") (pinfunction "VSS_4") (pintype "passive"))
      (node (ref "P1") (pin "1") (pinfunction "1_1") (pintype "passive"))
      (node (ref "P4") (pin "1") (pinfunction "1_1") (pintype "passive"))
      (node (ref "P5") (pin "1") (pinfunction "1_1") (pintype "passive"))
      (node (ref "R10") (pin "1") (pinfunction "1_1") (pintype "passive"))
      (node (ref "R12") (pin "1") (pinfunction "1_1") (pintype "passive"))
      (node (ref "R14") (pin "1") (pinfunction "1_1") (pintype "passive"))
      (node (ref "R2") (pin "1") (pinfunction "1_1") (pintype "passive"))
      (node (ref "R9") (pin "1") (pinfunction "1_1") (pintype "passive"))
      (node (ref "SW1") (pin "3") (pinfunction "3_3") (pintype "passive"))
      (node (ref "SW1") (pin "4") (pinfunction "4_4") (pintype "passive"))
      (node (ref "U1") (pin "1") (pinfunction "GND_1") (pintype "passive"))
      (node (ref "U2") (pin "22") (pinfunction "GND_22") (pintype "passive"))
    )
    (net (code "6") (name "Net-(C45-Pad1)") (class "Default")
      (node (ref "C45") (pin "1") (pinfunction "1_1") (pintype "passive"))
      (node (ref "P2") (pin "2") (pinfunction "2_2") (pintype "passive"))
      (node (ref "R3") (pin "2") (pinfunction "2_2") (pintype "passive"))
    )
    (net (code "7") (name "Net-(C45-Pad2)") (class "Default")
      (node (ref "C45") (pin "2") (pinfunction "2_2") (pintype "passive"))
      (node (ref "C49") (pin "1") (pinfunction "1_1") (pintype "passive"))
      (node (ref "R5") (pin "1") (pinfunction "1_1") (pintype "passive"))
    )
    (net (code "8") (name "Net-(C46-Pad1)") (class "Default")
      (node (ref "C46") (pin "1") (pinfunction "1_1") (pintype "passive"))
      (node (ref "P3") (pin "1") (pinfunction "1_1") (pintype "passive"))
      (node (ref "R4") (pin "2") (pinfunction "2_2") (pintype "passive"))
    )
    (net (code "9") (name "Net-(C46-Pad2)") (class "Default")
      (node (ref "C46") (pin "2") (pinfunction "2_2") (pintype "passive"))
      (node (ref "C50") (pin "1") (pinfunction "1_1") (pintype "passive"))
      (node (ref "R6") (pin "1") (pinfunction "1_1") (pintype "passive"))
    )
    (net (code "10") (name "Net-(D1-A)") (class "Default")
      (node (ref "D1") (pin "2") (pinfunction "A_2") (pintype "passive"))
      (node (ref "P1") (pin "2") (pinfunction "2_2") (pintype "passive"))
    )
    (net (code "11") (name "Net-(D1-K)") (class "Default")
      (node (ref "C1") (pin "2") (pinfunction "2_2") (pintype "passive"))
      (node (ref "D1") (pin "1") (pinfunction "K_1") (pintype "passive"))
      (node (ref "U1") (pin "3") (pinfunction "VIN_3") (pintype "passive"))
    )
    (net (code "12") (name "Net-(D2-A)") (class "Default")
      (node (ref "C3") (pin "2") (pinfunction "2_2") (pintype "passive"))
      (node (ref "C4") (pin "2") (pinfunction "2_2") (pintype "passive"))
      (node (ref "C5") (pin "2") (pinfunction "2_2") (pintype "passive"))
      (node (ref "D2") (pin "2") (pinfunction "A_2") (pintype "passive"))
      (node (ref "L1") (pin "2") (pinfunction "2_2") (pintype "passive"))
      (node (ref "R1") (pin "2") (pinfunction "2_2") (pintype "passive"))
    )
    (net (code "13") (name "Net-(LED1-DOUT)") (class "Default")
      (node (ref "LED1") (pin "3") (pinfunction "DOUT_3") (pintype "passive"))
      (node (ref "LED2") (pin "1") (pinfunction "DIN_1") (pintype "passive"))
    )
    (net (code "14") (name "Net-(LED2-DOUT)") (class "Default")
      (node (ref "LED2") (pin "3") (pinfunction "DOUT_3") (pintype "passive"))
      (node (ref "LED3") (pin "1") (pinfunction "DIN_1") (pintype "passive"))
    )
    (net (code "15") (name "Net-(LED3-DOUT)") (class "Default")
      (node (ref "LED3") (pin "3") (pinfunction "DOUT_3") (pintype "passive"))
      (node (ref "LED4") (pin "1") (pinfunction "DIN_1") (pintype "passive"))
    )
    (net (code "16") (name "Net-(LED4-DOUT)") (class "Default")
      (node (ref "LED4") (pin "3") (pinfunction "DOUT_3") (pintype "passive"))
      (node (ref "LED5") (pin "1") (pinfunction "DIN_1") (pintype "passive"))
    )
    (net (code "17") (name "Net-(LED5-DOUT)") (class "Default")
      (node (ref "LED5") (pin "3") (pinfunction "DOUT_3") (pintype "passive"))
      (node (ref "LED6") (pin "1") (pinfunction "DIN_1") (pintype "passive"))
    )
    (net (code "18") (name "Net-(LED6-DOUT)") (class "Default")
      (node (ref "LED6") (pin "3") (pinfunction "DOUT_3") (pintype "passive"))
      (node (ref "LED7") (pin "1") (pinfunction "DIN_1") (pintype "passive"))
    )
    (net (code "19") (name "Net-(LED7-DOUT)") (class "Default")
      (node (ref "LED7") (pin "3") (pinfunction "DOUT_3") (pintype "passive"))
      (node (ref "LED8") (pin "1") (pinfunction "DIN_1") (pintype "passive"))
    )
    (net (code "20") (name "Net-(LED8-DOUT)") (class "Default")
      (node (ref "LED8") (pin "3") (pinfunction "DOUT_3") (pintype "passive"))
      (node (ref "LED9") (pin "1") (pinfunction "DIN_1") (pintype "passive"))
    )
    (net (code "21") (name "Net-(LED10-DIN)") (class "Default")
      (node (ref "LED10") (pin "1") (pinfunction "DIN_1") (pintype "passive"))
      (node (ref "LED9") (pin "3") (pinfunction "DOUT_3") (pintype "passive"))
    )
    (net (code "22") (name "Net-(LED10-DOUT)") (class "Default")
      (node (ref "LED10") (pin "3") (pinfunction "DOUT_3") (pintype "passive"))
      (node (ref "LED11") (pin "1") (pinfunction "DIN_1") (pintype "passive"))
    )
    (net (code "23") (name "Net-(LED11-DOUT)") (class "Default")
      (node (ref "LED11") (pin "3") (pinfunction "DOUT_3") (pintype "passive"))
      (node (ref "LED12") (pin "1") (pinfunction "DIN_1") (pintype "passive"))
    )
    (net (code "24") (name "Net-(LED12-DOUT)") (class "Default")
      (node (ref "LED12") (pin "3") (pinfunction "DOUT_3") (pintype "passive"))
      (node (ref "LED13") (pin "1") (pinfunction "DIN_1") (pintype "passive"))
    )
    (net (code "25") (name "Net-(LED13-DOUT)") (class "Default")
      (node (ref "LED13") (pin "3") (pinfunction "DOUT_3") (pintype "passive"))
      (node (ref "LED14") (pin "1") (pinfunction "DIN_1") (pintype "passive"))
    )
    (net (code "26") (name "Net-(LED14-DOUT)") (class "Default")
      (node (ref "LED14") (pin "3") (pinfunction "DOUT_3") (pintype "passive"))
      (node (ref "LED15") (pin "1") (pinfunction "DIN_1") (pintype "passive"))
    )
    (net (code "27") (name "Net-(LED15-DOUT)") (class "Default")
      (node (ref "LED15") (pin "3") (pinfunction "DOUT_3") (pintype "passive"))
      (node (ref "LED16") (pin "1") (pinfunction "DIN_1") (pintype "passive"))
    )
    (net (code "28") (name "Net-(LED16-DOUT)") (class "Default")
      (node (ref "LED16") (pin "3") (pinfunction "DOUT_3") (pintype "passive"))
      (node (ref "LED17") (pin "1") (pinfunction "DIN_1") (pintype "passive"))
    )
    (net (code "29") (name "Net-(LED17-DOUT)") (class "Default")
      (node (ref "LED17") (pin "3") (pinfunction "DOUT_3") (pintype "passive"))
      (node (ref "LED18") (pin "1") (pinfunction "DIN_1") (pintype "passive"))
    )
    (net (code "30") (name "Net-(LED18-DOUT)") (class "Default")
      (node (ref "LED18") (pin "3") (pinfunction "DOUT_3") (pintype "passive"))
      (node (ref "LED19") (pin "1") (pinfunction "DIN_1") (pintype "passive"))
    )
    (net (code "31") (name "Net-(LED19-DOUT)") (class "Default")
      (node (ref "LED19") (pin "3") (pinfunction "DOUT_3") (pintype "passive"))
      (node (ref "LED20") (pin "1") (pinfunction "DIN_1") (pintype "passive"))
    )
    (net (code "32") (name "Net-(LED20-DOUT)") (class "Default")
      (node (ref "LED20") (pin "3") (pinfunction "DOUT_3") (pintype "passive"))
      (node (ref "LED21") (pin "1") (pinfunction "DIN_1") (pintype "passive"))
    )
    (net (code "33") (name "Net-(LED21-DOUT)") (class "Default")
      (node (ref "LED21") (pin "3") (pinfunction "DOUT_3") (pintype "passive"))
      (node (ref "LED22") (pin "1") (pinfunction "DIN_1") (pintype "passive"))
    )
    (net (code "34") (name "Net-(LED22-DOUT)") (class "Default")
      (node (ref "LED22") (pin "3") (pinfunction "DOUT_3") (pintype "passive"))
      (node (ref "LED23") (pin "1") (pinfunction "DIN_1") (pintype "passive"))
    )
    (net (code "35") (name "Net-(LED23-DOUT)") (class "Default")
      (node (ref "LED23") (pin "3") (pinfunction "DOUT_3") (pintype "passive"))
      (node (ref "LED24") (pin "1") (pinfunction "DIN_1") (pintype "passive"))
    )
    (net (code "36") (name "Net-(LED24-DOUT)") (class "Default")
      (node (ref "LED24") (pin "3") (pinfunction "DOUT_3") (pintype "passive"))
      (node (ref "LED25") (pin "1") (pinfunction "DIN_1") (pintype "passive"))
    )
    (net (code "37") (name "Net-(LED25-DOUT)") (class "Default")
      (node (ref "LED25") (pin "3") (pinfunction "DOUT_3") (pintype "passive"))
      (node (ref "LED26") (pin "1") (pinfunction "DIN_1") (pintype "passive"))
    )
    (net (code "38") (name "Net-(LED26-DOUT)") (class "Default")
      (node (ref "LED26") (pin "3") (pinfunction "DOUT_3") (pintype "passive"))
      (node (ref "LED27") (pin "1") (pinfunction "DIN_1") (pintype "passive"))
    )
    (net (code "39") (name "Net-(LED27-DOUT)") (class "Default")
      (node (ref "LED27") (pin "3") (pinfunction "DOUT_3") (pintype "passive"))
      (node (ref "LED28") (pin "1") (pinfunction "DIN_1") (pintype "passive"))
    )
    (net (code "40") (name "Net-(LED28-DOUT)") (class "Default")
      (node (ref "LED28") (pin "3") (pinfunction "DOUT_3") (pintype "passive"))
      (node (ref "LED29") (pin "1") (pinfunction "DIN_1") (pintype "passive"))
    )
    (net (code "41") (name "Net-(LED29-DOUT)") (class "Default")
      (node (ref "LED29") (pin "3") (pinfunction "DOUT_3") (pintype "passive"))
      (node (ref "LED30") (pin "1") (pinfunction "DIN_1") (pintype "passive"))
    )
    (net (code "42") (name "Net-(LED30-DOUT)") (class "Default")
      (node (ref "LED30") (pin "3") (pinfunction "DOUT_3") (pintype "passive"))
      (node (ref "LED31") (pin "1") (pinfunction "DIN_1") (pintype "passive"))
    )
    (net (code "43") (name "Net-(LED31-DOUT)") (class "Default")
      (node (ref "LED31") (pin "3") (pinfunction "DOUT_3") (pintype "passive"))
      (node (ref "LED32") (pin "1") (pinfunction "DIN_1") (pintype "passive"))
    )
    (net (code "44") (name "Net-(LED32-DOUT)") (class "Default")
      (node (ref "LED32") (pin "3") (pinfunction "DOUT_3") (pintype "passive"))
      (node (ref "LED33") (pin "1") (pinfunction "DIN_1") (pintype "passive"))
    )
    (net (code "45") (name "Net-(LED33-DOUT)") (class "Default")
      (node (ref "LED33") (pin "3") (pinfunction "DOUT_3") (pintype "passive"))
      (node (ref "LED34") (pin "1") (pinfunction "DIN_1") (pintype "passive"))
    )
    (net (code "46") (name "Net-(LED34-DOUT)") (class "Default")
      (node (ref "LED34") (pin "3") (pinfunction "DOUT_3") (pintype "passive"))
      (node (ref "LED35") (pin "1") (pinfunction "DIN_1") (pintype "passive"))
    )
    (net (code "47") (name "Net-(LED35-DOUT)") (class "Default")
      (node (ref "LED35") (pin "3") (pinfunction "DOUT_3") (pintype "passive"))
      (node (ref "LED36") (pin "1") (pinfunction "DIN_1") (pintype "passive"))
    )
    (net (code "48") (name "Net-(LED43-DOUT)") (class "Default")
      (node (ref "LED43") (pin "3") (pinfunction "DOUT_3") (pintype "passive"))
      (node (ref "LED44") (pin "1") (pinfunction "DIN_1") (pintype "passive"))
    )
    (net (code "49") (name "Net-(LED44-DOUT)") (class "Default")
      (node (ref "LED44") (pin "3") (pinfunction "DOUT_3") (pintype "passive"))
      (node (ref "LED45") (pin "1") (pinfunction "DIN_1") (pintype "passive"))
    )
    (net (code "50") (name "Net-(LED45-DOUT)") (class "Default")
      (node (ref "LED45") (pin "3") (pinfunction "DOUT_3") (pintype "passive"))
      (node (ref "LED46") (pin "1") (pinfunction "DIN_1") (pintype "passive"))
    )
    (net (code "51") (name "Net-(LED46-DOUT)") (class "Default")
      (node (ref "LED46") (pin "3") (pinfunction "DOUT_3") (pintype "passive"))
      (node (ref "LED47") (pin "1") (pinfunction "DIN_1") (pintype "passive"))
    )
    (net (code "52") (name "Net-(LED47-DOUT)") (class "Default")
      (node (ref "LED47") (pin "3") (pinfunction "DOUT_3") (pintype "passive"))
      (node (ref "LED48") (pin "1") (pinfunction "DIN_1") (pintype "passive"))
    )
    (net (code "53") (name "Net-(LED48-DOUT)") (class "Default")
      (node (ref "LED48") (pin "3") (pinfunction "DOUT_3") (pintype "passive"))
      (node (ref "LED49") (pin "1") (pinfunction "DIN_1") (pintype "passive"))
    )
    (net (code "54") (name "Net-(LED49-DOUT)") (class "Default")
      (node (ref "LED49") (pin "3") (pinfunction "DOUT_3") (pintype "passive"))
      (node (ref "LED50") (pin "1") (pinfunction "DIN_1") (pintype "passive"))
    )
    (net (code "55") (name "Net-(LED50-DOUT)") (class "Default")
      (node (ref "LED50") (pin "3") (pinfunction "DOUT_3") (pintype "passive"))
      (node (ref "LED51") (pin "1") (pinfunction "DIN_1") (pintype "passive"))
    )
    (net (code "56") (name "Net-(LED51-DOUT)") (class "Default")
      (node (ref "LED51") (pin "3") (pinfunction "DOUT_3") (pintype "passive"))
      (node (ref "LED52") (pin "1") (pinfunction "DIN_1") (pintype "passive"))
    )
    (net (code "57") (name "Net-(LED52-DOUT)") (class "Default")
      (node (ref "LED52") (pin "3") (pinfunction "DOUT_3") (pintype "passive"))
      (node (ref "LED53") (pin "1") (pinfunction "DIN_1") (pintype "passive"))
    )
    (net (code "58") (name "Net-(LED53-DOUT)") (class "Default")
      (node (ref "LED53") (pin "3") (pinfunction "DOUT_3") (pintype "passive"))
      (node (ref "LED54") (pin "1") (pinfunction "DIN_1") (pintype "passive"))
    )
    (net (code "59") (name "Net-(LED54-DOUT)") (class "Default")
      (node (ref "LED54") (pin "3") (pinfunction "DOUT_3") (pintype "passive"))
      (node (ref "LED55") (pin "1") (pinfunction "DIN_1") (pintype "passive"))
    )
    (net (code "60") (name "Net-(LED55-DOUT)") (class "Default")
      (node (ref "LED55") (pin "3") (pinfunction "DOUT_3") (pintype "passive"))
      (node (ref "LED56") (pin "1") (pinfunction "DIN_1") (pintype "passive"))
    )
    (net (code "61") (name "Net-(LED56-DOUT)") (class "Default")
      (node (ref "LED56") (pin "3") (pinfunction "DOUT_3") (pintype "passive"))
      (node (ref "LED57") (pin "1") (pinfunction "DIN_1") (pintype "passive"))
    )
    (net (code "62") (name "Net-(LED57-DOUT)") (class "Default")
      (node (ref "LED57") (pin "3") (pinfunction "DOUT_3") (pintype "passive"))
      (node (ref "LED58") (pin "1") (pinfunction "DIN_1") (pintype "passive"))
    )
    (net (code "63") (name "Net-(LED58-DOUT)") (class "Default")
      (node (ref "LED58") (pin "3") (pinfunction "DOUT_3") (pintype "passive"))
      (node (ref "LED59") (pin "1") (pinfunction "DIN_1") (pintype "passive"))
    )
    (net (code "64") (name "Net-(LED59-DOUT)") (class "Default")
      (node (ref "LED59") (pin "3") (pinfunction "DOUT_3") (pintype "passive"))
      (node (ref "LED60") (pin "1") (pinfunction "DIN_1") (pintype "passive"))
    )
    (net (code "65") (name "Net-(LED60-DOUT)") (class "Default")
      (node (ref "LED60") (pin "3") (pinfunction "DOUT_3") (pintype "passive"))
      (node (ref "LED61") (pin "1") (pinfunction "DIN_1") (pintype "passive"))
    )
    (net (code "66") (name "Net-(LED61-DOUT)") (class "Default")
      (node (ref "LED61") (pin "3") (pinfunction "DOUT_3") (pintype "passive"))
      (node (ref "LED62") (pin "1") (pinfunction "DIN_1") (pintype "passive"))
    )
    (net (code "67") (name "Net-(LED62-DOUT)") (class "Default")
      (node (ref "LED62") (pin "3") (pinfunction "DOUT_3") (pintype "passive"))
      (node (ref "LED63") (pin "1") (pinfunction "DIN_1") (pintype "passive"))
    )
    (net (code "68") (name "Net-(LED63-DOUT)") (class "Default")
      (node (ref "LED63") (pin "3") (pinfunction "DOUT_3") (pintype "passive"))
      (node (ref "LED64") (pin "1") (pinfunction "DIN_1") (pintype "passive"))
    )
    (net (code "69") (name "Net-(LED64-DOUT)") (class "Default")
      (node (ref "LED64") (pin "3") (pinfunction "DOUT_3") (pintype "passive"))
      (node (ref "LED65") (pin "1") (pinfunction "DIN_1") (pintype "passive"))
    )
    (net (code "70") (name "Net-(LED65-DOUT)") (class "Default")
      (node (ref "LED65") (pin "3") (pinfunction "DOUT_3") (pintype "passive"))
      (node (ref "LED66") (pin "1") (pinfunction "DIN_1") (pintype "passive"))
    )
    (net (code "71") (name "Net-(LED66-DOUT)") (class "Default")
      (node (ref "LED66") (pin "3") (pinfunction "DOUT_3") (pintype "passive"))
      (node (ref "LED67") (pin "1") (pinfunction "DIN_1") (pintype "passive"))
    )
    (net (code "72") (name "Net-(LED67-DOUT)") (class "Default")
      (node (ref "LED67") (pin "3") (pinfunction "DOUT_3") (pintype "passive"))
      (node (ref "LED68") (pin "1") (pinfunction "DIN_1") (pintype "passive"))
    )
    (net (code "73") (name "Net-(LED68-DOUT)") (class "Default")
      (node (ref "LED68") (pin "3") (pinfunction "DOUT_3") (pintype "passive"))
      (node (ref "LED69") (pin "1") (pinfunction "DIN_1") (pintype "passive"))
    )
    (net (code "74") (name "Net-(LED69-DOUT)") (class "Default")
      (node (ref "LED69") (pin "3") (pinfunction "DOUT_3") (pintype "passive"))
      (node (ref "LED70") (pin "1") (pinfunction "DIN_1") (pintype "passive"))
    )
    (net (code "75") (name "Net-(LED70-DOUT)") (class "Default")
      (node (ref "LED70") (pin "3") (pinfunction "DOUT_3") (pintype "passive"))
      (node (ref "LED71") (pin "1") (pinfunction "DIN_1") (pintype "passive"))
    )
    (net (code "76") (name "Net-(LED71-DOUT)") (class "Default")
      (node (ref "LED71") (pin "3") (pinfunction "DOUT_3") (pintype "passive"))
      (node (ref "LED72") (pin "1") (pinfunction "DIN_1") (pintype "passive"))
    )
    (net (code "77") (name "Net-(LED72-DOUT)") (class "Default")
      (node (ref "LED72") (pin "3") (pinfunction "DOUT_3") (pintype "passive"))
      (node (ref "LED73") (pin "1") (pinfunction "DIN_1") (pintype "passive"))
    )
    (net (code "78") (name "Net-(LED73-DOUT)") (class "Default")
      (node (ref "LED73") (pin "3") (pinfunction "DOUT_3") (pintype "passive"))
      (node (ref "LED74") (pin "1") (pinfunction "DIN_1") (pintype "passive"))
    )
    (net (code "79") (name "Net-(LED74-DOUT)") (class "Default")
      (node (ref "LED74") (pin "3") (pinfunction "DOUT_3") (pintype "passive"))
      (node (ref "LED75") (pin "1") (pinfunction "DIN_1") (pintype "passive"))
    )
    (net (code "80") (name "Net-(LED75-DOUT)") (class "Default")
      (node (ref "LED75") (pin "3") (pinfunction "DOUT_3") (pintype "passive"))
      (node (ref "LED76") (pin "1") (pinfunction "DIN_1") (pintype "passive"))
    )
    (net (code "81") (name "Net-(LED76-DOUT)") (class "Default")
      (node (ref "LED76") (pin "3") (pinfunction "DOUT_3") (pintype "passive"))
      (node (ref "LED77") (pin "1") (pinfunction "DIN_1") (pintype "passive"))
    )
    (net (code "82") (name "Net-(LED77-DOUT)") (class "Default")
      (node (ref "LED77") (pin "3") (pinfunction "DOUT_3") (pintype "passive"))
      (node (ref "LED78") (pin "1") (pinfunction "DIN_1") (pintype "passive"))
    )
    (net (code "83") (name "Net-(P2-Pad1)") (class "Default")
      (node (ref "P2") (pin "1") (pinfunction "1_1") (pintype "passive"))
      (node (ref "R3") (pin "1") (pinfunction "1_1") (pintype "passive"))
    )
    (net (code "84") (name "Net-(P3-Pad2)") (class "Default")
      (node (ref "P3") (pin "2") (pinfunction "2_2") (pintype "passive"))
      (node (ref "R4") (pin "1") (pinfunction "1_1") (pintype "passive"))
    )
    (net (code "85") (name "Net-(P4-Pad2)") (class "Default")
      (node (ref "P4") (pin "2") (pinfunction "2_2") (pintype "passive"))
      (node (ref "R7") (pin "2") (pinfunction "2_2") (pintype "passive"))
    )
    (net (code "86") (name "Net-(P5-Pad2)") (class "Default")
      (node (ref "P5") (pin "2") (pinfunction "2_2") (pintype "passive"))
      (node (ref "R8") (pin "2") (pinfunction "2_2") (pintype "passive"))
    )
    (net (code "87") (name "Net-(U1-BOOT)") (class "Default")
      (node (ref "C2") (pin "1") (pinfunction "1_1") (pintype "passive"))
      (node (ref "U1") (pin "6") (pinfunction "BOOT_6") (pintype "passive"))
    )
    (net (code "88") (name "Net-(U1-FB)") (class "Default")
      (node (ref "C3") (pin "1") (pinfunction "1_1") (pintype "passive"))
      (node (ref "R1") (pin "1") (pinfunction "1_1") (pintype "passive"))
      (node (ref "R2") (pin "2") (pinfunction "2_2") (pintype "passive"))
      (node (ref "U1") (pin "4") (pinfunction "FB_4") (pintype "passive"))
    )
    (net (code "89") (name "Net-(U1-SW)") (class "Default")
      (node (ref "C2") (pin "2") (pinfunction "2_2") (pintype "passive"))
      (node (ref "L1") (pin "1") (pinfunction "1_1") (pintype "passive"))
      (node (ref "U1") (pin "2") (pinfunction "SW_2") (pintype "passive"))
    )
    (net (code "90") (name "Net-(U2-GP2)") (class "Default")
      (node (ref "C47") (pin "2") (pinfunction "2_2") (pintype "passive"))
      (node (ref "R7") (pin "1") (pinfunction "1_1") (pintype "passive"))
      (node (ref "R9") (pin "2") (pinfunction "2_2") (pintype "passive"))
      (node (ref "U2") (pin "3") (pinfunction "GP2_3") (pintype "passive"))
    )
    (net (code "91") (name "Net-(U2-GP3)") (class "Default")
      (node (ref "C48") (pin "2") (pinfunction "2_2") (pintype "passive"))
      (node (ref "R10") (pin "2") (pinfunction "2_2") (pintype "passive"))
      (node (ref "R8") (pin "1") (pinfunction "1_1") (pintype "passive"))
      (node (ref "U2") (pin "4") (pinfunction "GP3_4") (pintype "passive"))
    )
    (net (code "92") (name "Net-(U2-GP8)") (class "Default")
      (node (ref "SW1") (pin "1") (pinfunction "1_1") (pintype "passive"))
      (node (ref "SW1") (pin "2") (pinfunction "2_2") (pintype "passive"))
      (node (ref "U2") (pin "9") (pinfunction "GP8_9") (pintype "passive"))
    )
    (net (code "93") (name "Net-(U2-GP27)") (class "Default")
      (node (ref "C7") (pin "2") (pinfunction "2_2") (pintype "passive"))
      (node (ref "R13") (pin "1") (pinfunction "1_1") (pintype "passive"))
      (node (ref "R14") (pin "2") (pinfunction "2_2") (pintype "passive"))
      (node (ref "R6") (pin "2") (pinfunction "2_2") (pintype "passive"))
      (node (ref "U2") (pin "18") (pinfunction "GP27_18") (pintype "passive"))
    )
    (net (code "94") (name "Net-(U2-GP28)") (class "Default")
      (node (ref "C8") (pin "2") (pinfunction "2_2") (pintype "passive"))
      (node (ref "R11") (pin "1") (pinfunction "1_1") (pintype "passive"))
      (node (ref "R12") (pin "2") (pinfunction "2_2") (pintype "passive"))
      (node (ref "R5") (pin "2") (pinfunction "2_2") (pintype "passive"))
      (node (ref "U2") (pin "19") (pinfunction "GP28_19") (pintype "passive"))
    )
    (net (code "95") (name "unconnected-(LED36-DOUT-Pad3)") (class "Default")
      (node (ref "LED36") (pin "3") (pinfunction "DOUT_3") (pintype "passive+no_connect"))
    )
    (net (code "96") (name "unconnected-(LED78-DOUT-Pad3)") (class "Default")
      (node (ref "LED78") (pin "3") (pinfunction "DOUT_3") (pintype "passive+no_connect"))
    )
    (net (code "97") (name "unconnected-(U1-EN-Pad5)") (class "Default")
      (node (ref "U1") (pin "5") (pinfunction "EN_5") (pintype "passive+no_connect"))
    )
    (net (code "98") (name "unconnected-(U2-GP0-Pad1)") (class "Default")
      (node (ref "U2") (pin "1") (pinfunction "GP0_1") (pintype "passive+no_connect"))
    )
    (net (code "99") (name "unconnected-(U2-GP1-Pad2)") (class "Default")
      (node (ref "U2") (pin "2") (pinfunction "GP1_2") (pintype "passive+no_connect"))
    )
    (net (code "100") (name "unconnected-(U2-GP4-Pad5)") (class "Default")
      (node (ref "U2") (pin "5") (pinfunction "GP4_5") (pintype "passive+no_connect"))
    )
    (net (code "101") (name "unconnected-(U2-GP5-Pad6)") (class "Default")
      (node (ref "U2") (pin "6") (pinfunction "GP5_6") (pintype "passive+no_connect"))
    )
    (net (code "102") (name "unconnected-(U2-GP6-Pad7)") (class "Default")
      (node (ref "U2") (pin "7") (pinfunction "GP6_7") (pintype "passive+no_connect"))
    )
    (net (code "103") (name "unconnected-(U2-GP7-Pad8)") (class "Default")
      (node (ref "U2") (pin "8") (pinfunction "GP7_8") (pintype "passive+no_connect"))
    )
    (net (code "104") (name "unconnected-(U2-GP9-Pad10)") (class "Default")
      (node (ref "U2") (pin "10") (pinfunction "GP9_10") (pintype "passive+no_connect"))
    )
    (net (code "105") (name "unconnected-(U2-GP10-Pad11)") (class "Default")
      (node (ref "U2") (pin "11") (pinfunction "GP10_11") (pintype "passive+no_connect"))
    )
    (net (code "106") (name "unconnected-(U2-GP11-Pad12)") (class "Default")
      (node (ref "U2") (pin "12") (pinfunction "GP11_12") (pintype "passive+no_connect"))
    )
    (net (code "107") (name "unconnected-(U2-GP12-Pad13)") (class "Default")
      (node (ref "U2") (pin "13") (pinfunction "GP12_13") (pintype "passive+no_connect"))
    )
    (net (code "108") (name "unconnected-(U2-GP13-Pad14)") (class "Default")
      (node (ref "U2") (pin "14") (pinfunction "GP13_14") (pintype "passive+no_connect"))
    )
    (net (code "109") (name "unconnected-(U2-GP26-Pad17)") (class "Default")
      (node (ref "U2") (pin "17") (pinfunction "GP26_17") (pintype "passive+no_connect"))
    )
    (net (code "110") (name "unconnected-(U2-GP29-Pad20)") (class "Default")
      (node (ref "U2") (pin "20") (pinfunction "GP29_20") (pintype "passive+no_connect"))
    )
  )
)
